# milliLearn-ice40-pcbng.net
KiCad netlist of a schematic drawn in EAGLE
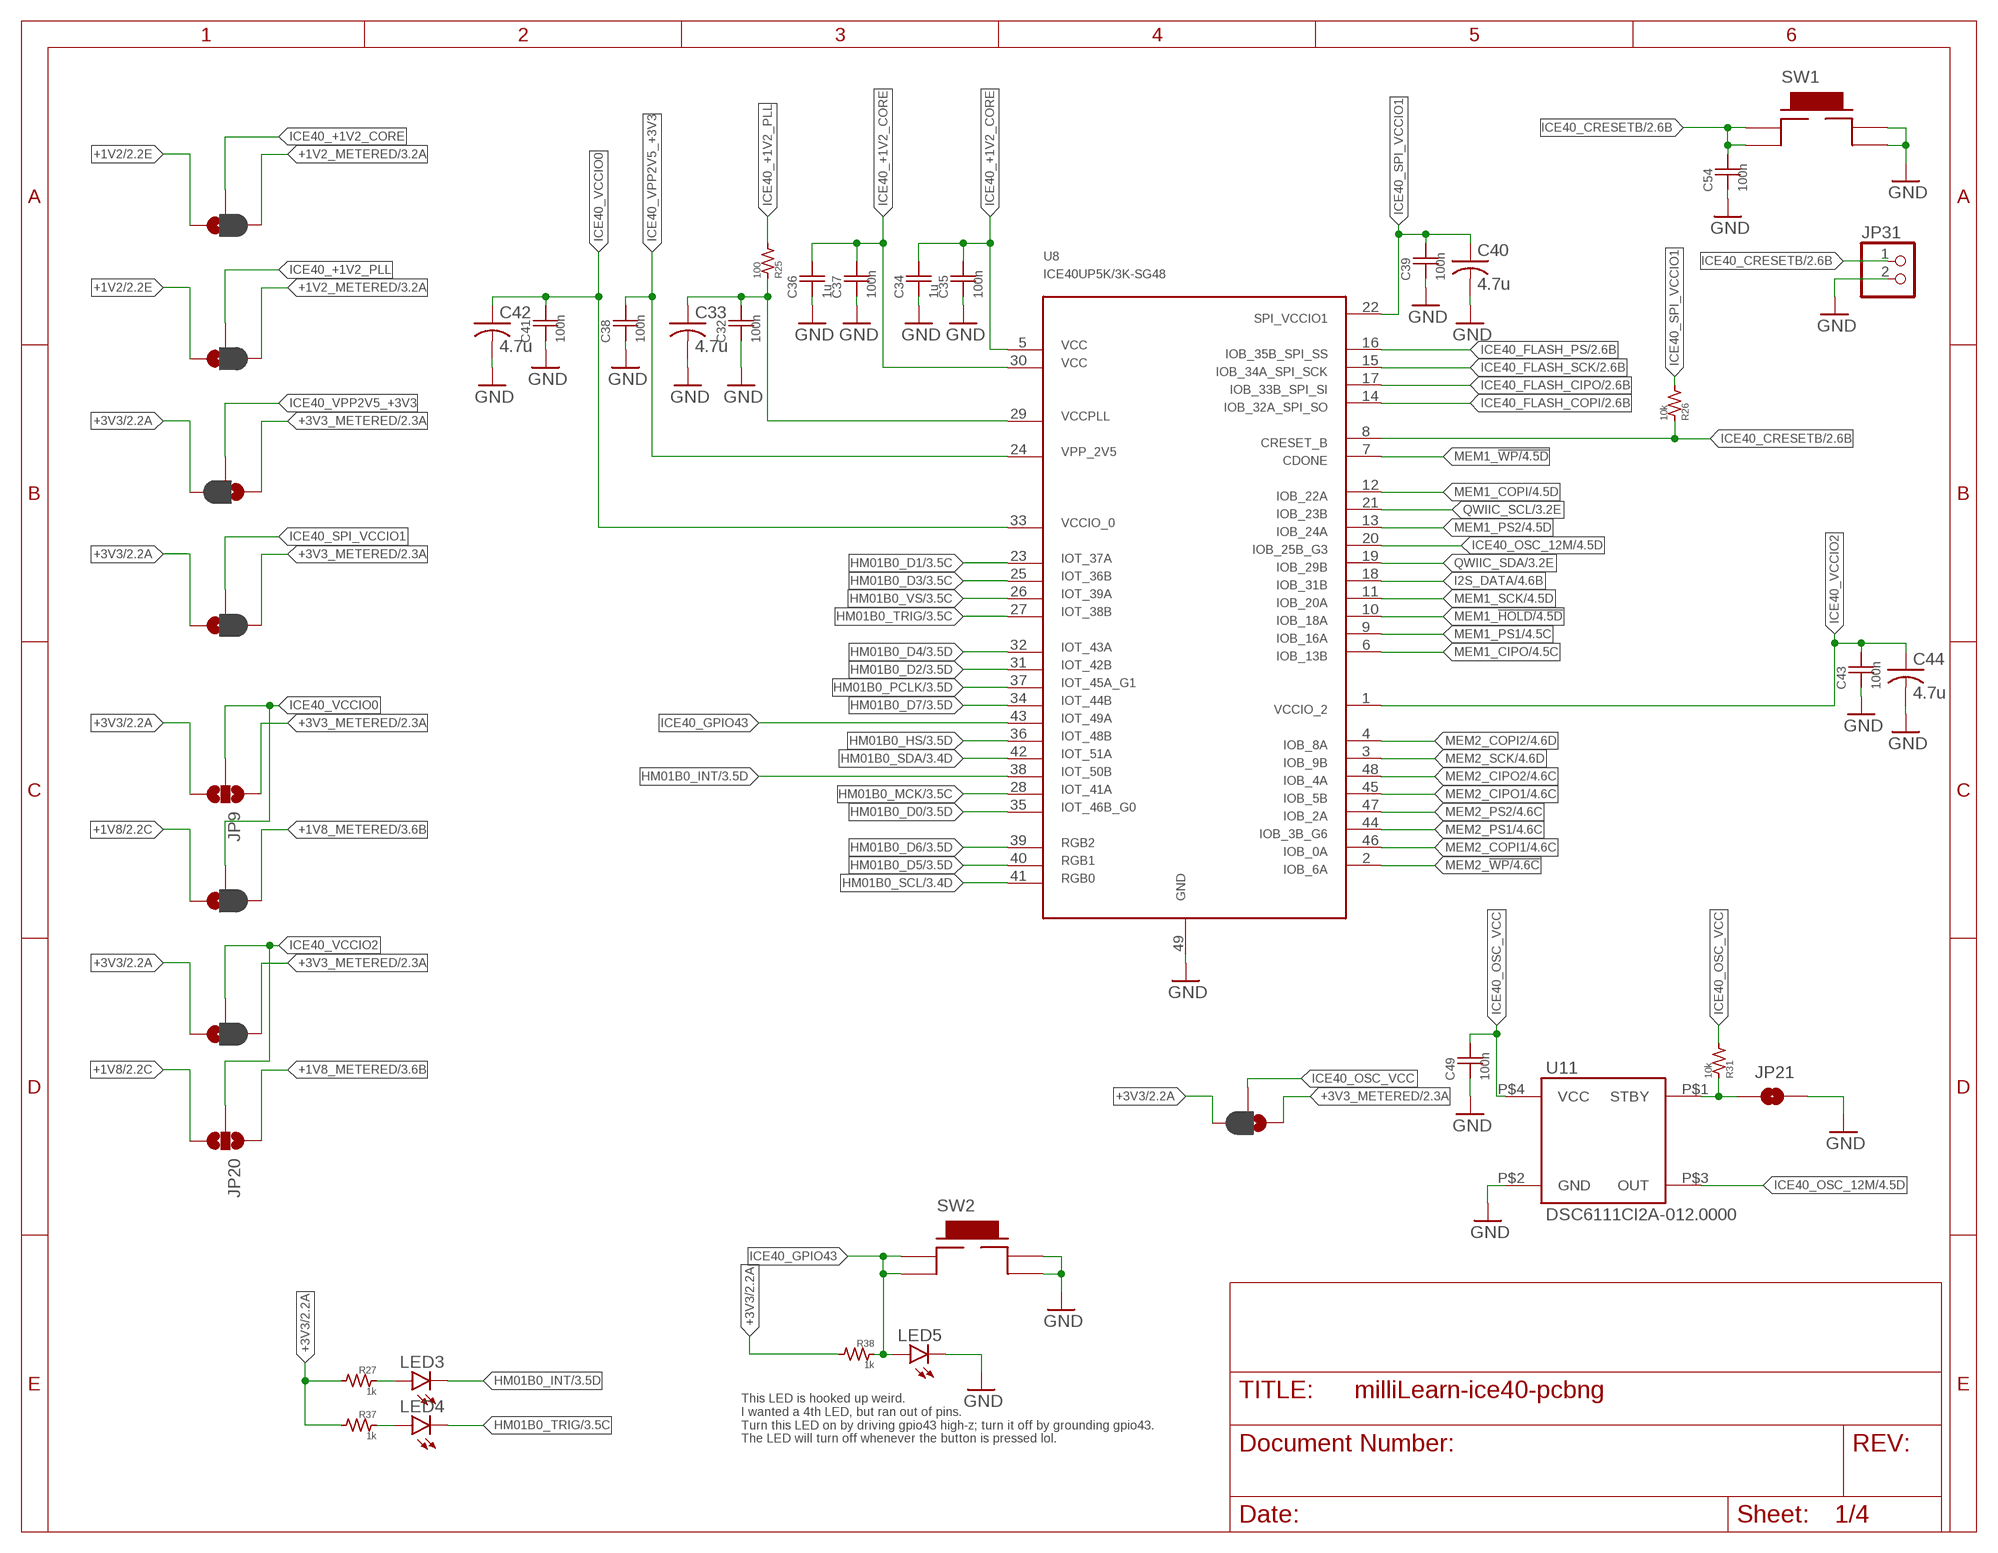
[diagram p0: schematic, sheet 1]
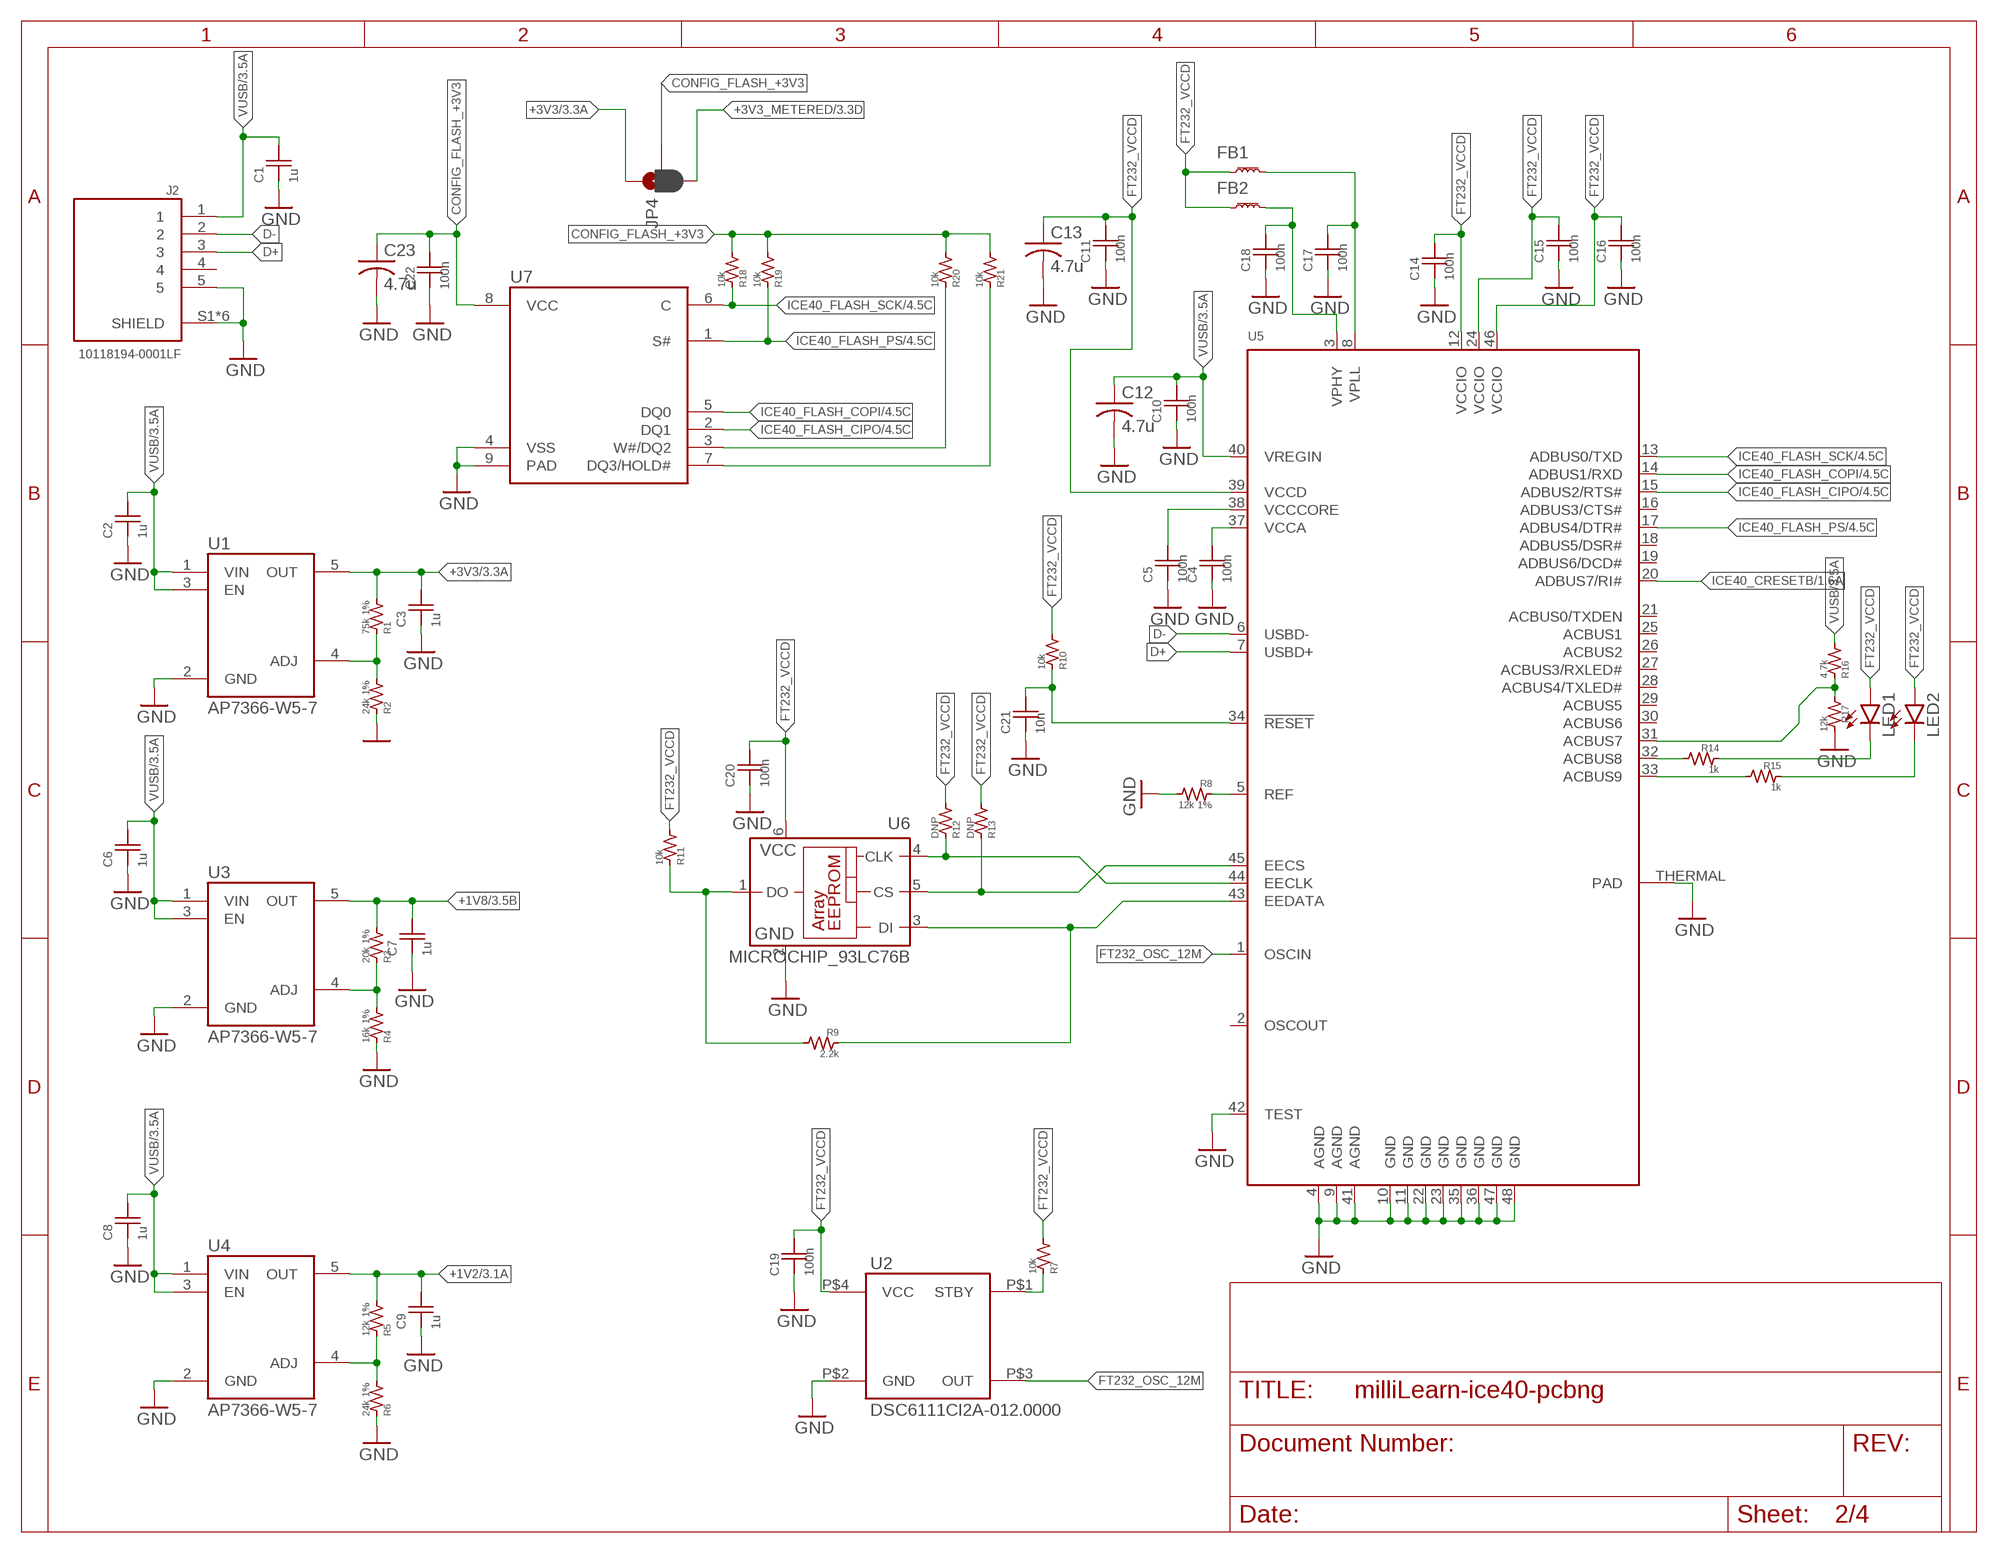
[diagram p1: schematic, sheet 2]
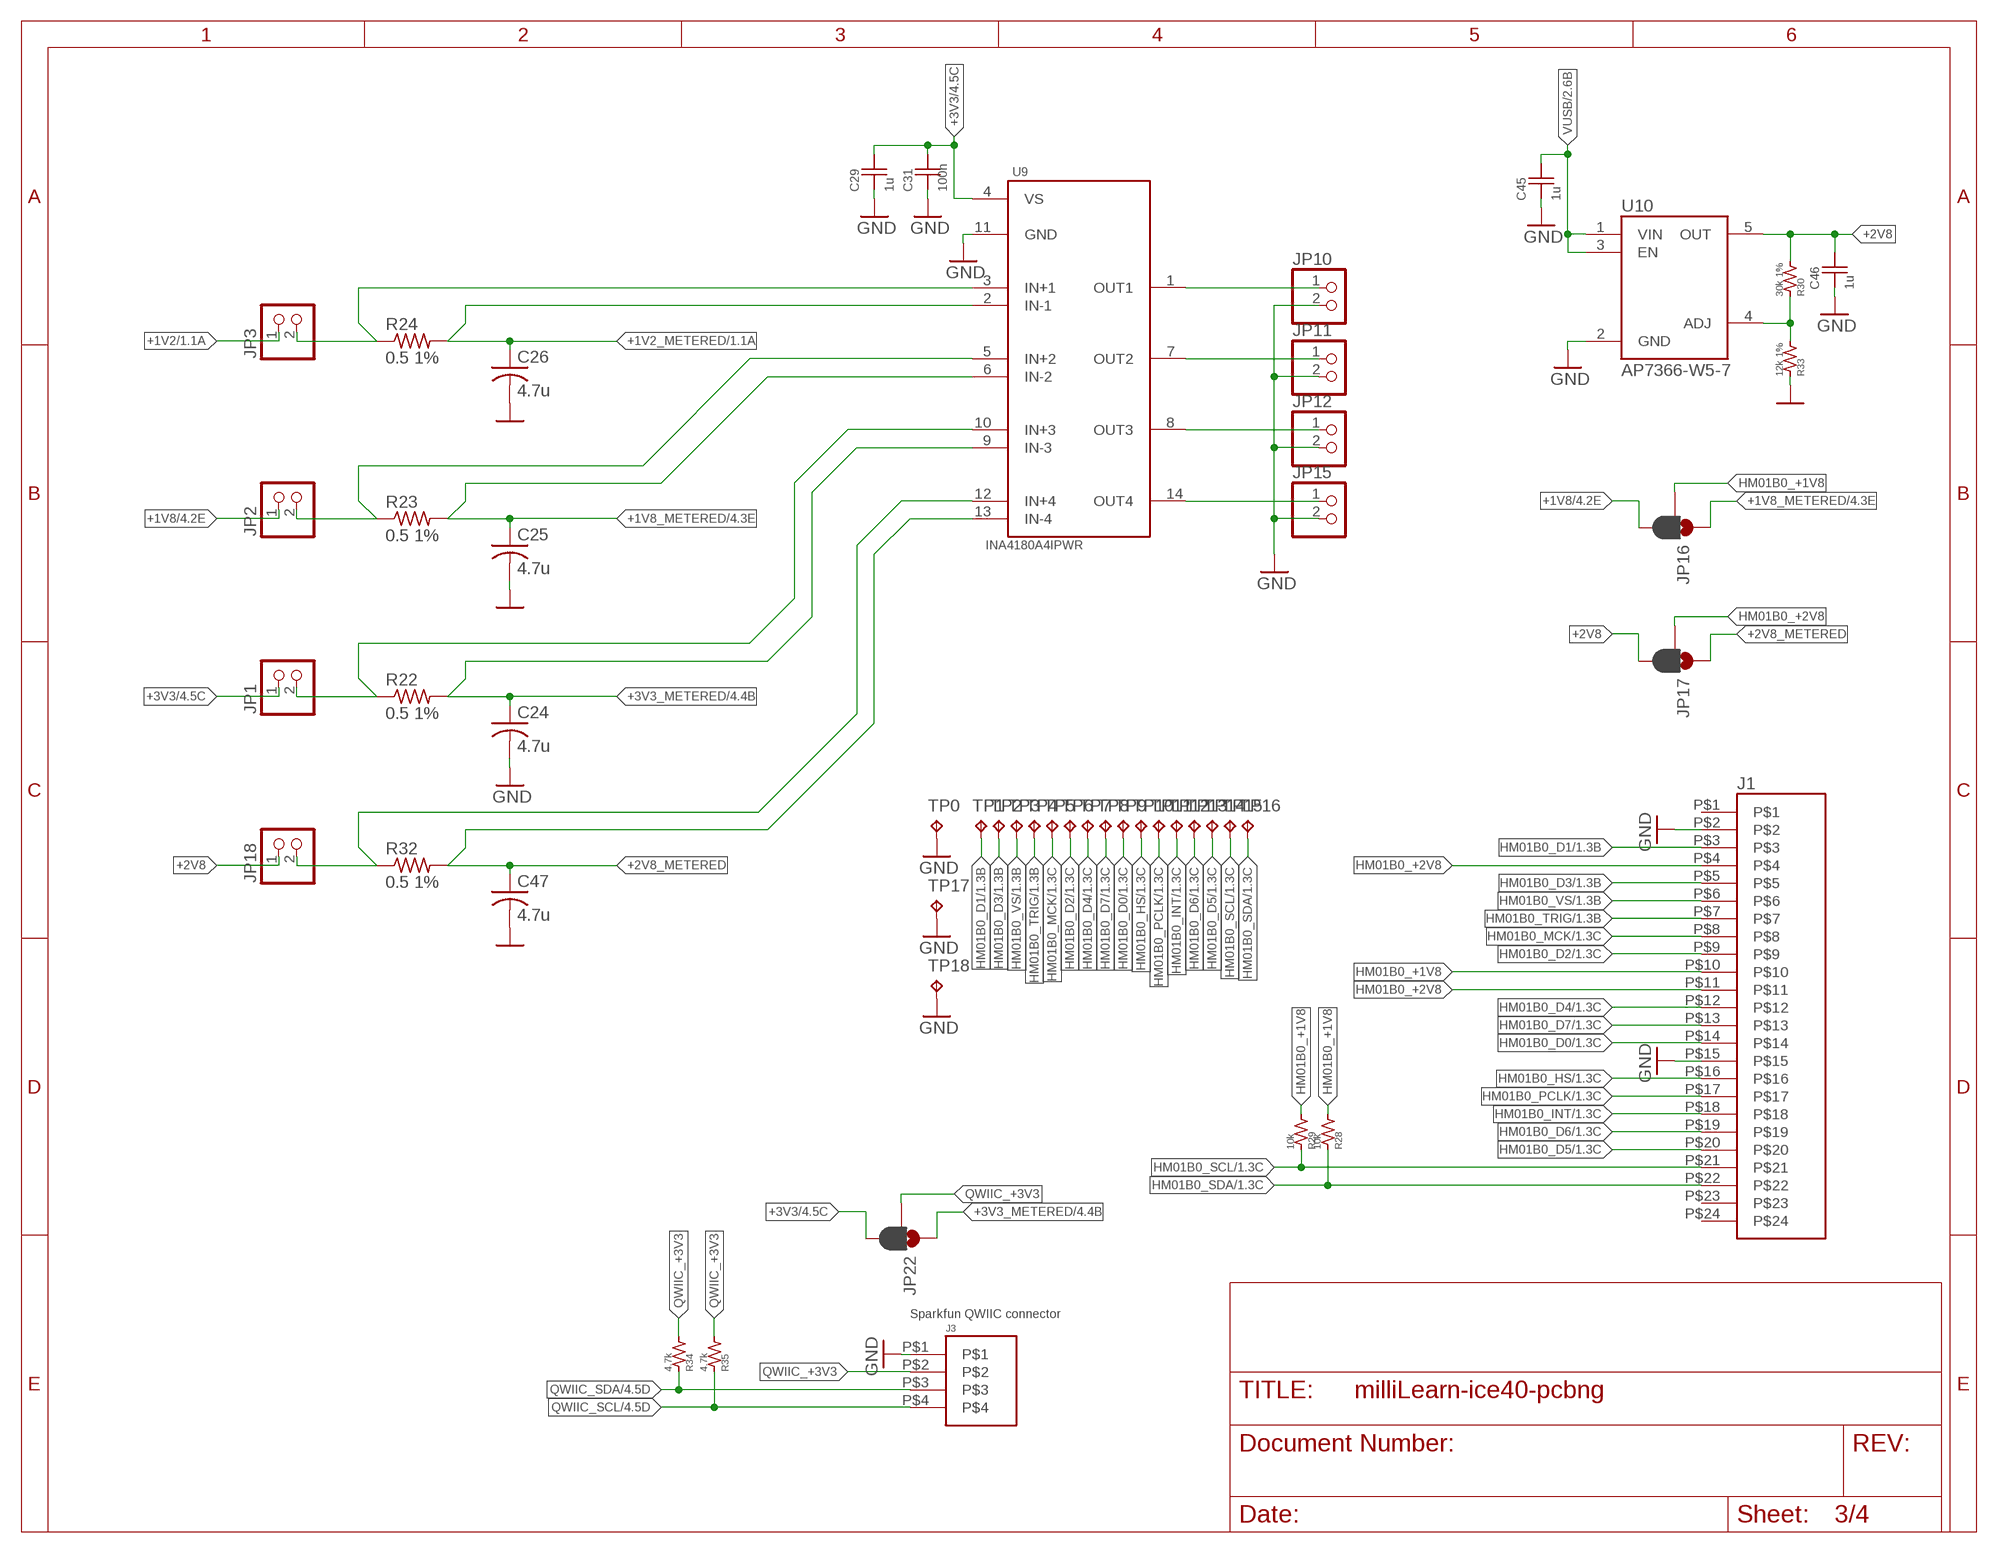
[diagram p2: schematic, sheet 3]
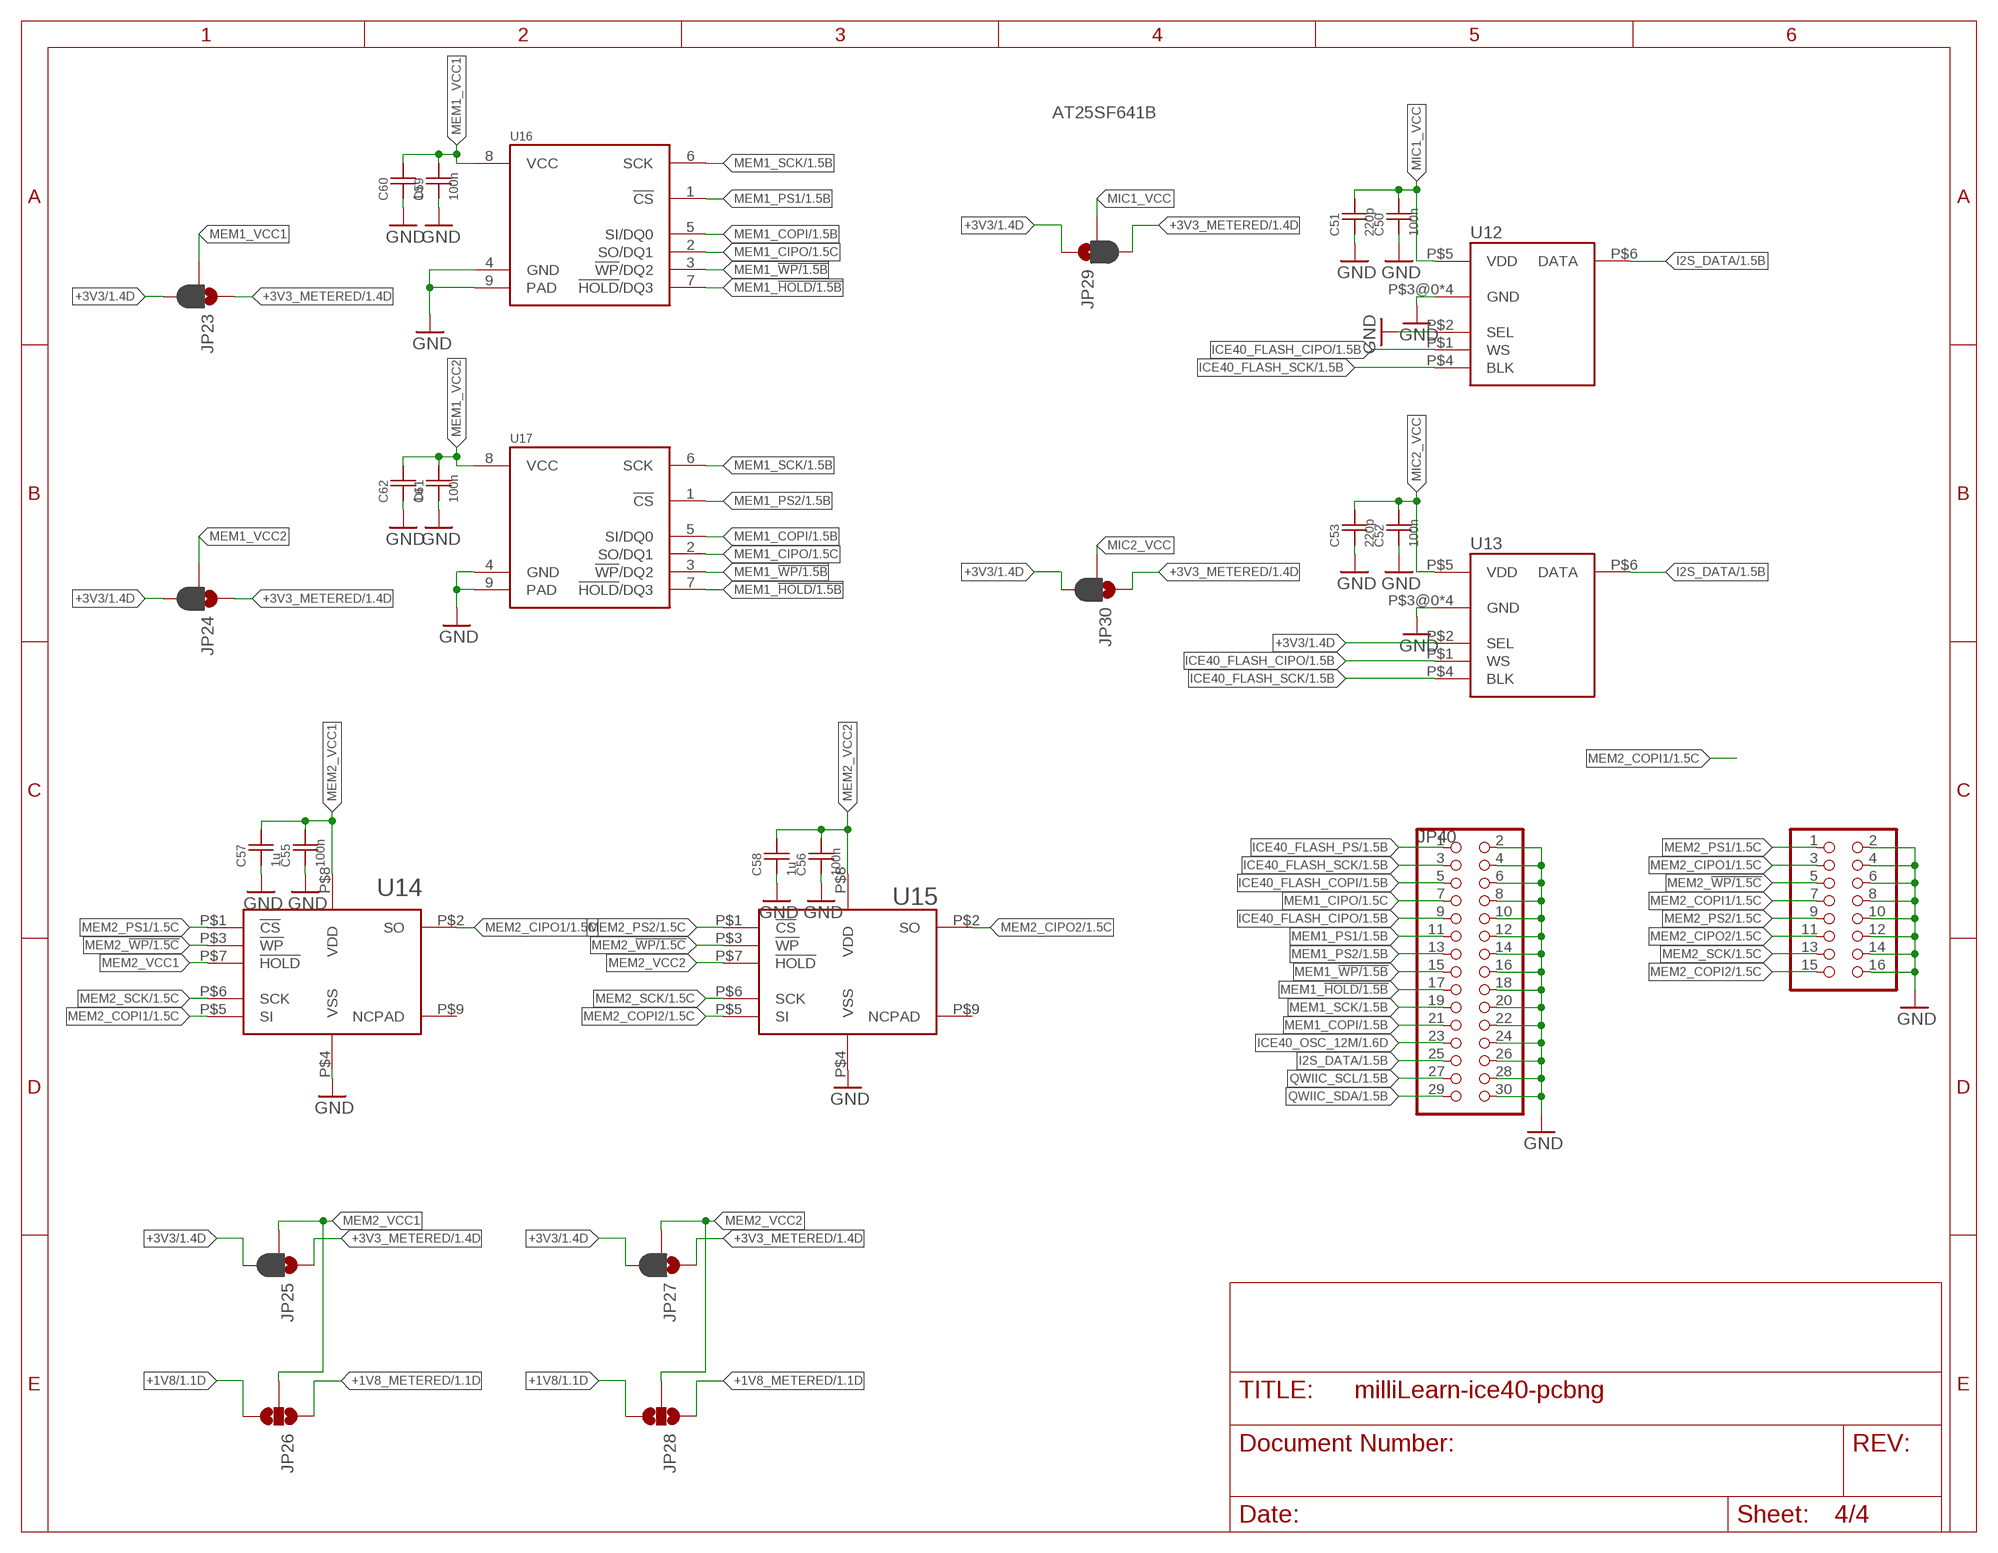
[diagram p3: schematic, sheet 4]

(export (version "E")
  (design (tool "Eeschema 10.0.6"))
  (components
    (comp (ref "C32")
      (value "100n")
      (footprint "eagle-import:C0402_COMPACT")
      (fields (field (name "MFR") "SAMSUNG"))
      (libsource (lib "eagle-import") (part "C0402_COMPACT"))
    )
    (comp (ref "C33")
      (value "4.7u")
      (footprint "eagle-import:C0603")
      (fields (field (name "MFR") "SAMSUNG"))
      (libsource (lib "eagle-import") (part "C-USC0603"))
    )
    (comp (ref "C34")
      (value "1u")
      (footprint "eagle-import:C0402_COMPACT")
      (fields (field (name "MFR") "SAMSUNG"))
      (libsource (lib "eagle-import") (part "C0402_COMPACT"))
    )
    (comp (ref "C35")
      (value "100n")
      (footprint "eagle-import:C0402_COMPACT")
      (fields (field (name "MFR") "SAMSUNG"))
      (libsource (lib "eagle-import") (part "C0402_COMPACT"))
    )
    (comp (ref "C36")
      (value "1u")
      (footprint "eagle-import:C0402_COMPACT")
      (fields (field (name "MFR") "SAMSUNG"))
      (libsource (lib "eagle-import") (part "C0402_COMPACT"))
    )
    (comp (ref "C37")
      (value "100n")
      (footprint "eagle-import:C0402_COMPACT")
      (fields (field (name "MFR") "SAMSUNG"))
      (libsource (lib "eagle-import") (part "C0402_COMPACT"))
    )
    (comp (ref "C38")
      (value "100n")
      (footprint "eagle-import:C0402_COMPACT")
      (fields (field (name "MFR") "SAMSUNG"))
      (libsource (lib "eagle-import") (part "C0402_COMPACT"))
    )
    (comp (ref "C39")
      (value "100n")
      (footprint "eagle-import:C0402_COMPACT")
      (fields (field (name "MFR") "SAMSUNG"))
      (libsource (lib "eagle-import") (part "C0402_COMPACT"))
    )
    (comp (ref "C40")
      (value "4.7u")
      (footprint "eagle-import:C0603")
      (fields (field (name "MFR") "SAMSUNG"))
      (libsource (lib "eagle-import") (part "C-USC0603"))
    )
    (comp (ref "C41")
      (value "100n")
      (footprint "eagle-import:C0402_COMPACT")
      (fields (field (name "MFR") "SAMSUNG"))
      (libsource (lib "eagle-import") (part "C0402_COMPACT"))
    )
    (comp (ref "C42")
      (value "4.7u")
      (footprint "eagle-import:C0603")
      (fields (field (name "MFR") "SAMSUNG"))
      (libsource (lib "eagle-import") (part "C-USC0603"))
    )
    (comp (ref "C43")
      (value "100n")
      (footprint "eagle-import:C0402_COMPACT")
      (fields (field (name "MFR") "SAMSUNG"))
      (libsource (lib "eagle-import") (part "C0402_COMPACT"))
    )
    (comp (ref "C44")
      (value "4.7u")
      (footprint "eagle-import:C0603")
      (fields (field (name "MFR") "SAMSUNG"))
      (libsource (lib "eagle-import") (part "C-USC0603"))
    )
    (comp (ref "C49")
      (value "100n")
      (footprint "eagle-import:C0402_COMPACT")
      (fields (field (name "MFR") "SAMSUNG"))
      (libsource (lib "eagle-import") (part "C0402_COMPACT"))
    )
    (comp (ref "C54")
      (value "100n")
      (footprint "eagle-import:C0402_COMPACT")
      (fields (field (name "MFR") "SAMSUNG"))
      (libsource (lib "eagle-import") (part "C0402_COMPACT"))
    )
    (comp (ref "JP5")
      (value "JUMPER-SMT_3_1-NC_PASTE_NO-SILK")
      (footprint "eagle-import:SMT-JUMPER_3_1-NC_PASTE_NO-SILK")
      (libsource (lib "eagle-import") (part "JUMPER-SMT_3_1-NC_PASTE_NO-SILK"))
    )
    (comp (ref "JP6")
      (value "JUMPER-SMT_3_1-NC_PASTE_NO-SILK")
      (footprint "eagle-import:SMT-JUMPER_3_1-NC_PASTE_NO-SILK")
      (libsource (lib "eagle-import") (part "JUMPER-SMT_3_1-NC_PASTE_NO-SILK"))
    )
    (comp (ref "JP7")
      (value "JUMPER-SMT_3_1-NC_PASTE_NO-SILK")
      (footprint "eagle-import:SMT-JUMPER_3_1-NC_PASTE_NO-SILK")
      (libsource (lib "eagle-import") (part "JUMPER-SMT_3_1-NC_PASTE_NO-SILK"))
    )
    (comp (ref "JP8")
      (value "JUMPER-SMT_3_1-NC_PASTE_NO-SILK")
      (footprint "eagle-import:SMT-JUMPER_3_1-NC_PASTE_NO-SILK")
      (libsource (lib "eagle-import") (part "JUMPER-SMT_3_1-NC_PASTE_NO-SILK"))
    )
    (comp (ref "JP9")
      (value "JUMPER-SMT_3_NO_NO-SILK")
      (footprint "eagle-import:SMT-JUMPER_3_NO_NO-SILK")
      (libsource (lib "eagle-import") (part "JUMPER-SMT_3_NO_NO-SILK"))
    )
    (comp (ref "JP13")
      (value "JUMPER-SMT_3_1-NC_PASTE_NO-SILK")
      (footprint "eagle-import:SMT-JUMPER_3_1-NC_PASTE_NO-SILK")
      (libsource (lib "eagle-import") (part "JUMPER-SMT_3_1-NC_PASTE_NO-SILK"))
    )
    (comp (ref "JP14")
      (value "JUMPER-SMT_3_1-NC_PASTE_NO-SILK")
      (footprint "eagle-import:SMT-JUMPER_3_1-NC_PASTE_NO-SILK")
      (libsource (lib "eagle-import") (part "JUMPER-SMT_3_1-NC_PASTE_NO-SILK"))
    )
    (comp (ref "JP19")
      (value "JUMPER-SMT_3_1-NC_PASTE_NO-SILK")
      (footprint "eagle-import:SMT-JUMPER_3_1-NC_PASTE_NO-SILK")
      (libsource (lib "eagle-import") (part "JUMPER-SMT_3_1-NC_PASTE_NO-SILK"))
    )
    (comp (ref "JP20")
      (value "JUMPER-SMT_3_NO_NO-SILK")
      (footprint "eagle-import:SMT-JUMPER_3_NO_NO-SILK")
      (libsource (lib "eagle-import") (part "JUMPER-SMT_3_NO_NO-SILK"))
    )
    (comp (ref "JP21")
      (value "JUMPER-SMT_2_NO_NO-SILK")
      (footprint "eagle-import:SMT-JUMPER_2_NO_NO-SILK")
      (libsource (lib "eagle-import") (part "JUMPER-SMT_2_NO_NO-SILK"))
    )
    (comp (ref "JP31")
      (value "PINHD-1X2")
      (footprint "eagle-import:1X02")
      (libsource (lib "eagle-import") (part "PINHD-1X2"))
    )
    (comp (ref "LED3")
      (value "LEDCHIPLED_0603")
      (footprint "eagle-import:CHIPLED_0603")
      (fields (field (name "MFR") "LITE-ON"))
      (libsource (lib "eagle-import") (part "LEDCHIPLED_0603"))
    )
    (comp (ref "LED4")
      (value "LEDCHIPLED_0603")
      (footprint "eagle-import:CHIPLED_0603")
      (fields (field (name "MFR") "LITE-ON"))
      (libsource (lib "eagle-import") (part "LEDCHIPLED_0603"))
    )
    (comp (ref "LED5")
      (value "LEDCHIPLED_0603")
      (footprint "eagle-import:CHIPLED_0603")
      (fields (field (name "MFR") "LITE-ON"))
      (libsource (lib "eagle-import") (part "LEDCHIPLED_0603"))
    )
    (comp (ref "R25")
      (value "100")
      (footprint "eagle-import:R0402_COMPACT")
      (fields (field (name "MFR") "YAGEO"))
      (libsource (lib "eagle-import") (part "R0402_COMPACT"))
    )
    (comp (ref "R26")
      (value "10k")
      (footprint "eagle-import:R0402_COMPACT")
      (fields (field (name "MFR") "PANASONIC"))
      (libsource (lib "eagle-import") (part "R0402_COMPACT"))
    )
    (comp (ref "R27")
      (value "1k")
      (footprint "eagle-import:R0402_COMPACT")
      (fields (field (name "MFR") "PANASONIC"))
      (libsource (lib "eagle-import") (part "R0402_COMPACT"))
    )
    (comp (ref "R31")
      (value "10k")
      (footprint "eagle-import:R0402_COMPACT")
      (fields (field (name "MFR") "PANASONIC"))
      (libsource (lib "eagle-import") (part "R0402_COMPACT"))
    )
    (comp (ref "R37")
      (value "1k")
      (footprint "eagle-import:R0402_COMPACT")
      (fields (field (name "MFR") "PANASONIC"))
      (libsource (lib "eagle-import") (part "R0402_COMPACT"))
    )
    (comp (ref "R38")
      (value "1k")
      (footprint "eagle-import:R0402_COMPACT")
      (fields (field (name "MFR") "PANASONIC"))
      (libsource (lib "eagle-import") (part "R0402_COMPACT"))
    )
    (comp (ref "SW1")
      (value "TE_FSMJSMA")
      (footprint "eagle-import:TE_FSMJSMA")
      (fields (field (name "MFR") "TE"))
      (libsource (lib "eagle-import") (part "TE_FSMJSMA"))
    )
    (comp (ref "SW2")
      (value "TE_FSMJSMA")
      (footprint "eagle-import:TE_FSMJSMA")
      (fields (field (name "MFR") "TE"))
      (libsource (lib "eagle-import") (part "TE_FSMJSMA"))
    )
    (comp (ref "U8")
      (value "ICE40UP5K/3K-SG48")
      (footprint "eagle-import:ICE40UP5K_3K-SG48")
      (fields (field (name "MFR") "LATTICE"))
      (libsource (lib "eagle-import") (part "ICE40UP5K/3K-SG48"))
    )
    (comp (ref "U11")
      (value "DSC6111CI2A-012.0000")
      (footprint "eagle-import:DSC6111CI2A-012.0000")
      (fields (field (name "MFR") "MICROCHIP"))
      (libsource (lib "eagle-import") (part "DSC6111CI2A-012.0000"))
    )
    (comp (ref "C24")
      (value "4.7u")
      (footprint "eagle-import:C0603")
      (fields (field (name "MFR") "SAMSUNG"))
      (libsource (lib "eagle-import") (part "C-USC0603"))
    )
    (comp (ref "C25")
      (value "4.7u")
      (footprint "eagle-import:C0603")
      (fields (field (name "MFR") "SAMSUNG"))
      (libsource (lib "eagle-import") (part "C-USC0603"))
    )
    (comp (ref "C26")
      (value "4.7u")
      (footprint "eagle-import:C0603")
      (fields (field (name "MFR") "SAMSUNG"))
      (libsource (lib "eagle-import") (part "C-USC0603"))
    )
    (comp (ref "C29")
      (value "1u")
      (footprint "eagle-import:C0402_COMPACT")
      (fields (field (name "MFR") "SAMSUNG"))
      (libsource (lib "eagle-import") (part "C0402_COMPACT"))
    )
    (comp (ref "C31")
      (value "100n")
      (footprint "eagle-import:C0402_COMPACT")
      (fields (field (name "MFR") "SAMSUNG"))
      (libsource (lib "eagle-import") (part "C0402_COMPACT"))
    )
    (comp (ref "C45")
      (value "1u")
      (footprint "eagle-import:C0402_COMPACT")
      (fields (field (name "MFR") "SAMSUNG"))
      (libsource (lib "eagle-import") (part "C0402_COMPACT"))
    )
    (comp (ref "C46")
      (value "1u")
      (footprint "eagle-import:C0402_COMPACT")
      (fields (field (name "MFR") "SAMSUNG"))
      (libsource (lib "eagle-import") (part "C0402_COMPACT"))
    )
    (comp (ref "C47")
      (value "4.7u")
      (footprint "eagle-import:C0603")
      (fields (field (name "MFR") "SAMSUNG"))
      (libsource (lib "eagle-import") (part "C-USC0603"))
    )
    (comp (ref "J1")
      (value "SFV24R-2STE1HLF")
      (footprint "eagle-import:SFV24R-2STE1HLF")
      (fields (field (name "MFR") "AMPHENOL"))
      (libsource (lib "eagle-import") (part "SFV24R-2STE1HLF"))
    )
    (comp (ref "J3")
      (value "SM04B-SRSS-TB(LF)(SN)")
      (footprint "eagle-import:SM04B-SRSS-TB(LF)(SN)")
      (fields (field (name "MFR") "JST"))
      (libsource (lib "eagle-import") (part "SM04B-SRSS-TB(LF)(SN)"))
    )
    (comp (ref "JP1")
      (value "PINHD-1X2")
      (footprint "eagle-import:1X02")
      (fields (field (name "MFR") "WURTH ELECTRONIK"))
      (libsource (lib "eagle-import") (part "PINHD-1X2"))
    )
    (comp (ref "JP2")
      (value "PINHD-1X2")
      (footprint "eagle-import:1X02")
      (fields (field (name "MFR") "WURTH ELECTRONIK"))
      (libsource (lib "eagle-import") (part "PINHD-1X2"))
    )
    (comp (ref "JP3")
      (value "PINHD-1X2")
      (footprint "eagle-import:1X02")
      (fields (field (name "MFR") "WURTH ELECTRONIK"))
      (libsource (lib "eagle-import") (part "PINHD-1X2"))
    )
    (comp (ref "JP10")
      (value "PINHD-1X2")
      (footprint "eagle-import:1X02")
      (fields (field (name "MFR") "WURTH ELECTRONIK"))
      (libsource (lib "eagle-import") (part "PINHD-1X2"))
    )
    (comp (ref "JP11")
      (value "PINHD-1X2")
      (footprint "eagle-import:1X02")
      (fields (field (name "MFR") "WURTH ELECTRONIK"))
      (libsource (lib "eagle-import") (part "PINHD-1X2"))
    )
    (comp (ref "JP12")
      (value "PINHD-1X2")
      (footprint "eagle-import:1X02")
      (fields (field (name "MFR") "WURTH ELECTRONIK"))
      (libsource (lib "eagle-import") (part "PINHD-1X2"))
    )
    (comp (ref "JP15")
      (value "PINHD-1X2")
      (footprint "eagle-import:1X02")
      (fields (field (name "MFR") "WURTH ELECTRONIK"))
      (libsource (lib "eagle-import") (part "PINHD-1X2"))
    )
    (comp (ref "JP16")
      (value "JUMPER-SMT_3_1-NC_PASTE_NO-SILK")
      (footprint "eagle-import:SMT-JUMPER_3_1-NC_PASTE_NO-SILK")
      (libsource (lib "eagle-import") (part "JUMPER-SMT_3_1-NC_PASTE_NO-SILK"))
    )
    (comp (ref "JP17")
      (value "JUMPER-SMT_3_1-NC_PASTE_NO-SILK")
      (footprint "eagle-import:SMT-JUMPER_3_1-NC_PASTE_NO-SILK")
      (libsource (lib "eagle-import") (part "JUMPER-SMT_3_1-NC_PASTE_NO-SILK"))
    )
    (comp (ref "JP18")
      (value "PINHD-1X2")
      (footprint "eagle-import:1X02")
      (fields (field (name "MFR") "WURTH ELECTRONIK"))
      (libsource (lib "eagle-import") (part "PINHD-1X2"))
    )
    (comp (ref "JP22")
      (value "JUMPER-SMT_3_1-NC_PASTE_NO-SILK")
      (footprint "eagle-import:SMT-JUMPER_3_1-NC_PASTE_NO-SILK")
      (libsource (lib "eagle-import") (part "JUMPER-SMT_3_1-NC_PASTE_NO-SILK"))
    )
    (comp (ref "R22")
      (value "0.5 1%")
      (footprint "eagle-import:R0603")
      (fields (field (name "MFR") "YAGEO"))
      (libsource (lib "eagle-import") (part "R-US_R0603"))
    )
    (comp (ref "R23")
      (value "0.5 1%")
      (footprint "eagle-import:R0603")
      (fields (field (name "MFR") "YAGEO"))
      (libsource (lib "eagle-import") (part "R-US_R0603"))
    )
    (comp (ref "R24")
      (value "0.5 1%")
      (footprint "eagle-import:R0603")
      (fields (field (name "MFR") "YAGEO"))
      (libsource (lib "eagle-import") (part "R-US_R0603"))
    )
    (comp (ref "R28")
      (value "10k")
      (footprint "eagle-import:R0402_COMPACT")
      (fields (field (name "MFR") "PANASONIC"))
      (libsource (lib "eagle-import") (part "R0402_COMPACT"))
    )
    (comp (ref "R29")
      (value "10k")
      (footprint "eagle-import:R0402_COMPACT")
      (fields (field (name "MFR") "PANASONIC"))
      (libsource (lib "eagle-import") (part "R0402_COMPACT"))
    )
    (comp (ref "R30")
      (value "30k 1%")
      (footprint "eagle-import:R0402_COMPACT")
      (fields (field (name "MFR") "PANASONIC"))
      (libsource (lib "eagle-import") (part "R0402_COMPACT"))
    )
    (comp (ref "R32")
      (value "0.5 1%")
      (footprint "eagle-import:R0603")
      (fields (field (name "MFR") "YAGEO"))
      (libsource (lib "eagle-import") (part "R-US_R0603"))
    )
    (comp (ref "R33")
      (value "12k 1%")
      (footprint "eagle-import:R0402_COMPACT")
      (fields (field (name "MFR") "PANASONIC"))
      (libsource (lib "eagle-import") (part "R0402_COMPACT"))
    )
    (comp (ref "R34")
      (value "4.7k")
      (footprint "eagle-import:R0402_COMPACT")
      (fields (field (name "MFR") "PANASONIC"))
      (libsource (lib "eagle-import") (part "R0402_COMPACT"))
    )
    (comp (ref "R35")
      (value "4.7k")
      (footprint "eagle-import:R0402_COMPACT")
      (fields (field (name "MFR") "PANASONIC"))
      (libsource (lib "eagle-import") (part "R0402_COMPACT"))
    )
    (comp (ref "TP0")
      (value "TPTP10SQ")
      (footprint "eagle-import:TP10SQ")
      (libsource (lib "eagle-import") (part "TPTP10SQ"))
    )
    (comp (ref "TP1")
      (value "TPTP10SQ")
      (footprint "eagle-import:TP10SQ")
      (libsource (lib "eagle-import") (part "TPTP10SQ"))
    )
    (comp (ref "TP2")
      (value "TPTP10SQ")
      (footprint "eagle-import:TP10SQ")
      (libsource (lib "eagle-import") (part "TPTP10SQ"))
    )
    (comp (ref "TP3")
      (value "TPTP10SQ")
      (footprint "eagle-import:TP10SQ")
      (libsource (lib "eagle-import") (part "TPTP10SQ"))
    )
    (comp (ref "TP4")
      (value "TPTP10SQ")
      (footprint "eagle-import:TP10SQ")
      (libsource (lib "eagle-import") (part "TPTP10SQ"))
    )
    (comp (ref "TP5")
      (value "TPTP10SQ")
      (footprint "eagle-import:TP10SQ")
      (libsource (lib "eagle-import") (part "TPTP10SQ"))
    )
    (comp (ref "TP6")
      (value "TPTP10SQ")
      (footprint "eagle-import:TP10SQ")
      (libsource (lib "eagle-import") (part "TPTP10SQ"))
    )
    (comp (ref "TP7")
      (value "TPTP10SQ")
      (footprint "eagle-import:TP10SQ")
      (libsource (lib "eagle-import") (part "TPTP10SQ"))
    )
    (comp (ref "TP8")
      (value "TPTP10SQ")
      (footprint "eagle-import:TP10SQ")
      (libsource (lib "eagle-import") (part "TPTP10SQ"))
    )
    (comp (ref "TP9")
      (value "TPTP10SQ")
      (footprint "eagle-import:TP10SQ")
      (libsource (lib "eagle-import") (part "TPTP10SQ"))
    )
    (comp (ref "TP10")
      (value "TPTP10SQ")
      (footprint "eagle-import:TP10SQ")
      (libsource (lib "eagle-import") (part "TPTP10SQ"))
    )
    (comp (ref "TP11")
      (value "TPTP10SQ")
      (footprint "eagle-import:TP10SQ")
      (libsource (lib "eagle-import") (part "TPTP10SQ"))
    )
    (comp (ref "TP12")
      (value "TPTP10SQ")
      (footprint "eagle-import:TP10SQ")
      (libsource (lib "eagle-import") (part "TPTP10SQ"))
    )
    (comp (ref "TP13")
      (value "TPTP10SQ")
      (footprint "eagle-import:TP10SQ")
      (libsource (lib "eagle-import") (part "TPTP10SQ"))
    )
    (comp (ref "TP14")
      (value "TPTP10SQ")
      (footprint "eagle-import:TP10SQ")
      (libsource (lib "eagle-import") (part "TPTP10SQ"))
    )
    (comp (ref "TP15")
      (value "TPTP10SQ")
      (footprint "eagle-import:TP10SQ")
      (libsource (lib "eagle-import") (part "TPTP10SQ"))
    )
    (comp (ref "TP16")
      (value "TPTP10SQ")
      (footprint "eagle-import:TP10SQ")
      (libsource (lib "eagle-import") (part "TPTP10SQ"))
    )
    (comp (ref "TP17")
      (value "TPTP10SQ")
      (footprint "eagle-import:TP10SQ")
      (libsource (lib "eagle-import") (part "TPTP10SQ"))
    )
    (comp (ref "TP18")
      (value "TPTP10SQ")
      (footprint "eagle-import:TP10SQ")
      (libsource (lib "eagle-import") (part "TPTP10SQ"))
    )
    (comp (ref "U9")
      (value "INA4180A4IPWR")
      (footprint "eagle-import:INA4180A4IPWR")
      (fields (field (name "MFR") "TI"))
      (libsource (lib "eagle-import") (part "INA4180A4IPWR"))
    )
    (comp (ref "U10")
      (value "AP7366-W5-7")
      (footprint "eagle-import:AP7366-W5-7")
      (fields (field (name "MFR") "Diodes Inc"))
      (libsource (lib "eagle-import") (part "AP7366-W5-7"))
    )
    (comp (ref "C50")
      (value "100n")
      (footprint "eagle-import:C0402_COMPACT")
      (fields (field (name "MFR") "SAMSUNG"))
      (libsource (lib "eagle-import") (part "C0402_COMPACT"))
    )
    (comp (ref "C51")
      (value "220p")
      (footprint "eagle-import:C0402_COMPACT")
      (fields (field (name "MFR") "SAMSUNG"))
      (libsource (lib "eagle-import") (part "C0402_COMPACT"))
    )
    (comp (ref "C52")
      (value "100n")
      (footprint "eagle-import:C0402_COMPACT")
      (fields (field (name "MFR") "SAMSUNG"))
      (libsource (lib "eagle-import") (part "C0402_COMPACT"))
    )
    (comp (ref "C53")
      (value "220p")
      (footprint "eagle-import:C0402_COMPACT")
      (fields (field (name "MFR") "SAMSUNG"))
      (libsource (lib "eagle-import") (part "C0402_COMPACT"))
    )
    (comp (ref "C55")
      (value "100n")
      (footprint "eagle-import:C0402_COMPACT")
      (fields (field (name "MFR") "SAMSUNG"))
      (libsource (lib "eagle-import") (part "C0402_COMPACT"))
    )
    (comp (ref "C56")
      (value "100n")
      (footprint "eagle-import:C0402_COMPACT")
      (fields (field (name "MFR") "SAMSUNG"))
      (libsource (lib "eagle-import") (part "C0402_COMPACT"))
    )
    (comp (ref "C57")
      (value "1u")
      (footprint "eagle-import:C0402_COMPACT")
      (fields (field (name "MFR") "SAMSUNG"))
      (libsource (lib "eagle-import") (part "C0402_COMPACT"))
    )
    (comp (ref "C58")
      (value "1u")
      (footprint "eagle-import:C0402_COMPACT")
      (fields (field (name "MFR") "SAMSUNG"))
      (libsource (lib "eagle-import") (part "C0402_COMPACT"))
    )
    (comp (ref "C59")
      (value "100n")
      (footprint "eagle-import:C0402_COMPACT")
      (fields (field (name "MFR") "SAMSUNG"))
      (libsource (lib "eagle-import") (part "C0402_COMPACT"))
    )
    (comp (ref "C60")
      (value "1u")
      (footprint "eagle-import:C0402_COMPACT")
      (fields (field (name "MFR") "SAMSUNG"))
      (libsource (lib "eagle-import") (part "C0402_COMPACT"))
    )
    (comp (ref "C61")
      (value "100n")
      (footprint "eagle-import:C0402_COMPACT")
      (fields (field (name "MFR") "SAMSUNG"))
      (libsource (lib "eagle-import") (part "C0402_COMPACT"))
    )
    (comp (ref "C62")
      (value "1u")
      (footprint "eagle-import:C0402_COMPACT")
      (fields (field (name "MFR") "SAMSUNG"))
      (libsource (lib "eagle-import") (part "C0402_COMPACT"))
    )
    (comp (ref "JP23")
      (value "JUMPER-SMT_3_1-NC_PASTE_NO-SILK")
      (footprint "eagle-import:SMT-JUMPER_3_1-NC_PASTE_NO-SILK")
      (libsource (lib "eagle-import") (part "JUMPER-SMT_3_1-NC_PASTE_NO-SILK"))
    )
    (comp (ref "JP24")
      (value "JUMPER-SMT_3_1-NC_PASTE_NO-SILK")
      (footprint "eagle-import:SMT-JUMPER_3_1-NC_PASTE_NO-SILK")
      (libsource (lib "eagle-import") (part "JUMPER-SMT_3_1-NC_PASTE_NO-SILK"))
    )
    (comp (ref "JP25")
      (value "JUMPER-SMT_3_1-NC_PASTE_NO-SILK")
      (footprint "eagle-import:SMT-JUMPER_3_1-NC_PASTE_NO-SILK")
      (libsource (lib "eagle-import") (part "JUMPER-SMT_3_1-NC_PASTE_NO-SILK"))
    )
    (comp (ref "JP26")
      (value "JUMPER-SMT_3_NO_NO-SILK")
      (footprint "eagle-import:SMT-JUMPER_3_NO_NO-SILK")
      (libsource (lib "eagle-import") (part "JUMPER-SMT_3_NO_NO-SILK"))
    )
    (comp (ref "JP27")
      (value "JUMPER-SMT_3_1-NC_PASTE_NO-SILK")
      (footprint "eagle-import:SMT-JUMPER_3_1-NC_PASTE_NO-SILK")
      (libsource (lib "eagle-import") (part "JUMPER-SMT_3_1-NC_PASTE_NO-SILK"))
    )
    (comp (ref "JP28")
      (value "JUMPER-SMT_3_NO_NO-SILK")
      (footprint "eagle-import:SMT-JUMPER_3_NO_NO-SILK")
      (libsource (lib "eagle-import") (part "JUMPER-SMT_3_NO_NO-SILK"))
    )
    (comp (ref "JP29")
      (value "JUMPER-SMT_3_1-NC_PASTE_NO-SILK")
      (footprint "eagle-import:SMT-JUMPER_3_1-NC_PASTE_NO-SILK")
      (libsource (lib "eagle-import") (part "JUMPER-SMT_3_1-NC_PASTE_NO-SILK"))
    )
    (comp (ref "JP30")
      (value "JUMPER-SMT_3_1-NC_PASTE_NO-SILK")
      (footprint "eagle-import:SMT-JUMPER_3_1-NC_PASTE_NO-SILK")
      (libsource (lib "eagle-import") (part "JUMPER-SMT_3_1-NC_PASTE_NO-SILK"))
    )
    (comp (ref "JP40")
      (value "PINHD-2X15")
      (footprint "eagle-import:2X15")
      (libsource (lib "eagle-import") (part "PINHD-2X15"))
    )
    (comp (ref "JP41")
      (value "PINHD-2X8")
      (footprint "eagle-import:2X08")
      (libsource (lib "eagle-import") (part "PINHD-2X8"))
    )
    (comp (ref "U12")
      (value "SPH0645LM4H-B")
      (footprint "eagle-import:SPH0645LM4H-B")
      (fields (field (name "MFR") "KNOWLES"))
      (libsource (lib "eagle-import") (part "SPH0645LM4H-B"))
    )
    (comp (ref "U13")
      (value "SPH0645LM4H-B")
      (footprint "eagle-import:SPH0645LM4H-B")
      (fields (field (name "MFR") "KNOWLES"))
      (libsource (lib "eagle-import") (part "SPH0645LM4H-B"))
    )
    (comp (ref "U14")
      (value "CY15B104Q-LHXI")
      (footprint "eagle-import:CY15B104Q-LHXI")
      (fields (field (name "MANUFACTURER") "Cypress") (field (name "MFR") "CYPRESS"))
      (libsource (lib "eagle-import") (part "CY15B104Q-LHXI"))
    )
    (comp (ref "U15")
      (value "CY15B104Q-LHXI")
      (footprint "eagle-import:CY15B104Q-LHXI")
      (fields (field (name "MANUFACTURER") "Cypress") (field (name "MFR") "CYPRESS"))
      (libsource (lib "eagle-import") (part "CY15B104Q-LHXI"))
    )
    (comp (ref "U16")
      (value "AT25QF641B-SHB-T")
      (footprint "eagle-import:AT25QF641B-SHB-T")
      (fields (field (name "MFR") "ADESTO"))
      (libsource (lib "eagle-import") (part "AT25QF641B-SHB-T"))
    )
    (comp (ref "U17")
      (value "AT25QF641B-SHB-T")
      (footprint "eagle-import:AT25QF641B-SHB-T")
      (fields (field (name "MFR") "ADESTO"))
      (libsource (lib "eagle-import") (part "AT25QF641B-SHB-T"))
    )
    (comp (ref "C1")
      (value "1u")
      (footprint "eagle-import:C0402_COMPACT")
      (fields (field (name "MFR") "SAMSUNG"))
      (libsource (lib "eagle-import") (part "C0402_COMPACT"))
    )
    (comp (ref "C2")
      (value "1u")
      (footprint "eagle-import:C0402_COMPACT")
      (fields (field (name "MFR") "SAMSUNG"))
      (libsource (lib "eagle-import") (part "C0402_COMPACT"))
    )
    (comp (ref "C3")
      (value "1u")
      (footprint "eagle-import:C0402_COMPACT")
      (fields (field (name "MFR") "SAMSUNG"))
      (libsource (lib "eagle-import") (part "C0402_COMPACT"))
    )
    (comp (ref "C4")
      (value "100n")
      (footprint "eagle-import:C0402_COMPACT")
      (fields (field (name "MFR") "SAMSUNG"))
      (libsource (lib "eagle-import") (part "C0402_COMPACT"))
    )
    (comp (ref "C5")
      (value "100n")
      (footprint "eagle-import:C0402_COMPACT")
      (fields (field (name "MFR") "SAMSUNG"))
      (libsource (lib "eagle-import") (part "C0402_COMPACT"))
    )
    (comp (ref "C6")
      (value "1u")
      (footprint "eagle-import:C0402_COMPACT")
      (fields (field (name "MFR") "SAMSUNG"))
      (libsource (lib "eagle-import") (part "C0402_COMPACT"))
    )
    (comp (ref "C7")
      (value "1u")
      (footprint "eagle-import:C0402_COMPACT")
      (fields (field (name "MFR") "SAMSUNG"))
      (libsource (lib "eagle-import") (part "C0402_COMPACT"))
    )
    (comp (ref "C8")
      (value "1u")
      (footprint "eagle-import:C0402_COMPACT")
      (fields (field (name "MFR") "SAMSUNG"))
      (libsource (lib "eagle-import") (part "C0402_COMPACT"))
    )
    (comp (ref "C9")
      (value "1u")
      (footprint "eagle-import:C0402_COMPACT")
      (fields (field (name "MFR") "SAMSUNG"))
      (libsource (lib "eagle-import") (part "C0402_COMPACT"))
    )
    (comp (ref "C10")
      (value "100n")
      (footprint "eagle-import:C0402_COMPACT")
      (fields (field (name "MFR") "SAMSUNG"))
      (libsource (lib "eagle-import") (part "C0402_COMPACT"))
    )
    (comp (ref "C11")
      (value "100n")
      (footprint "eagle-import:C0402_COMPACT")
      (fields (field (name "MFR") "SAMSUNG"))
      (libsource (lib "eagle-import") (part "C0402_COMPACT"))
    )
    (comp (ref "C12")
      (value "4.7u")
      (footprint "eagle-import:C0603")
      (fields (field (name "MFR") "SAMSUNG"))
      (libsource (lib "eagle-import") (part "C-USC0603"))
    )
    (comp (ref "C13")
      (value "4.7u")
      (footprint "eagle-import:C0603")
      (fields (field (name "MFR") "SAMSUNG"))
      (libsource (lib "eagle-import") (part "C-USC0603"))
    )
    (comp (ref "C14")
      (value "100n")
      (footprint "eagle-import:C0402_COMPACT")
      (fields (field (name "MFR") "SAMSUNG"))
      (libsource (lib "eagle-import") (part "C0402_COMPACT"))
    )
    (comp (ref "C15")
      (value "100n")
      (footprint "eagle-import:C0402_COMPACT")
      (fields (field (name "MFR") "SAMSUNG"))
      (libsource (lib "eagle-import") (part "C0402_COMPACT"))
    )
    (comp (ref "C16")
      (value "100n")
      (footprint "eagle-import:C0402_COMPACT")
      (fields (field (name "MFR") "SAMSUNG"))
      (libsource (lib "eagle-import") (part "C0402_COMPACT"))
    )
    (comp (ref "C17")
      (value "100n")
      (footprint "eagle-import:C0402_COMPACT")
      (fields (field (name "MFR") "SAMSUNG"))
      (libsource (lib "eagle-import") (part "C0402_COMPACT"))
    )
    (comp (ref "C18")
      (value "100n")
      (footprint "eagle-import:C0402_COMPACT")
      (fields (field (name "MFR") "SAMSUNG"))
      (libsource (lib "eagle-import") (part "C0402_COMPACT"))
    )
    (comp (ref "C19")
      (value "100n")
      (footprint "eagle-import:C0402_COMPACT")
      (fields (field (name "MFR") "SAMSUNG"))
      (libsource (lib "eagle-import") (part "C0402_COMPACT"))
    )
    (comp (ref "C20")
      (value "100n")
      (footprint "eagle-import:C0402_COMPACT")
      (fields (field (name "MFR") "SAMSUNG"))
      (libsource (lib "eagle-import") (part "C0402_COMPACT"))
    )
    (comp (ref "C21")
      (value "10n")
      (footprint "eagle-import:C0402_COMPACT")
      (fields (field (name "MFR") "SAMSUNG"))
      (libsource (lib "eagle-import") (part "C0402_COMPACT"))
    )
    (comp (ref "C22")
      (value "100n")
      (footprint "eagle-import:C0402_COMPACT")
      (fields (field (name "MFR") "SAMSUNG"))
      (libsource (lib "eagle-import") (part "C0402_COMPACT"))
    )
    (comp (ref "C23")
      (value "4.7u")
      (footprint "eagle-import:C0603")
      (fields (field (name "MFR") "SAMSUNG"))
      (libsource (lib "eagle-import") (part "C-USC0603"))
    )
    (comp (ref "FB1")
      (value "BLM18KG601SN1D")
      (footprint "eagle-import:BLM18KG601SN1D")
      (fields (field (name "MFR") "MURATA"))
      (libsource (lib "eagle-import") (part "BLM18KG601SN1D"))
    )
    (comp (ref "FB2")
      (value "BLM18KG601SN1D")
      (footprint "eagle-import:BLM18KG601SN1D")
      (fields (field (name "MFR") "MURATA"))
      (libsource (lib "eagle-import") (part "BLM18KG601SN1D"))
    )
    (comp (ref "J2")
      (value "10118194-0001LF")
      (footprint "eagle-import:AMPHENOL_10118194-0001LF")
      (fields (field (name "MF") "Amphenol ICC"))
      (libsource (lib "eagle-import") (part "10118194-0001LF"))
    )
    (comp (ref "JP4")
      (value "JUMPER-SMT_3_1-NC_PASTE_NO-SILK")
      (footprint "eagle-import:SMT-JUMPER_3_1-NC_PASTE_NO-SILK")
      (libsource (lib "eagle-import") (part "JUMPER-SMT_3_1-NC_PASTE_NO-SILK"))
    )
    (comp (ref "LED1")
      (value "LEDCHIPLED_0603")
      (footprint "eagle-import:CHIPLED_0603")
      (fields (field (name "MFR") "LITE-ON"))
      (libsource (lib "eagle-import") (part "LEDCHIPLED_0603"))
    )
    (comp (ref "LED2")
      (value "LEDCHIPLED_0603")
      (footprint "eagle-import:CHIPLED_0603")
      (fields (field (name "MFR") "LITE-ON"))
      (libsource (lib "eagle-import") (part "LEDCHIPLED_0603"))
    )
    (comp (ref "R1")
      (value "75k 1%")
      (footprint "eagle-import:R0402_COMPACT")
      (fields (field (name "MFR") "PANASONIC"))
      (libsource (lib "eagle-import") (part "R0402_COMPACT"))
    )
    (comp (ref "R2")
      (value "24k 1%")
      (footprint "eagle-import:R0402_COMPACT")
      (fields (field (name "MFR") "PANASONIC"))
      (libsource (lib "eagle-import") (part "R0402_COMPACT"))
    )
    (comp (ref "R3")
      (value "20k 1%")
      (footprint "eagle-import:R0402_COMPACT")
      (fields (field (name "MFR") "PANASONIC"))
      (libsource (lib "eagle-import") (part "R0402_COMPACT"))
    )
    (comp (ref "R4")
      (value "16k 1%")
      (footprint "eagle-import:R0402_COMPACT")
      (fields (field (name "MFR") "PANASONIC"))
      (libsource (lib "eagle-import") (part "R0402_COMPACT"))
    )
    (comp (ref "R5")
      (value "12k 1%")
      (footprint "eagle-import:R0402_COMPACT")
      (fields (field (name "MFR") "PANASONIC"))
      (libsource (lib "eagle-import") (part "R0402_COMPACT"))
    )
    (comp (ref "R6")
      (value "24k 1%")
      (footprint "eagle-import:R0402_COMPACT")
      (fields (field (name "MFR") "PANASONIC"))
      (libsource (lib "eagle-import") (part "R0402_COMPACT"))
    )
    (comp (ref "R7")
      (value "10k")
      (footprint "eagle-import:R0402_COMPACT")
      (fields (field (name "MFR") "PANASONIC"))
      (libsource (lib "eagle-import") (part "R0402_COMPACT"))
    )
    (comp (ref "R8")
      (value "12k 1%")
      (footprint "eagle-import:R0402_COMPACT")
      (fields (field (name "MFR") "PANASONIC"))
      (libsource (lib "eagle-import") (part "R0402_COMPACT"))
    )
    (comp (ref "R9")
      (value "2.2k")
      (footprint "eagle-import:R0402_COMPACT")
      (fields (field (name "MFR") "PANASONIC"))
      (libsource (lib "eagle-import") (part "R0402_COMPACT"))
    )
    (comp (ref "R10")
      (value "10k")
      (footprint "eagle-import:R0402_COMPACT")
      (fields (field (name "MFR") "PANASONIC"))
      (libsource (lib "eagle-import") (part "R0402_COMPACT"))
    )
    (comp (ref "R11")
      (value "10k")
      (footprint "eagle-import:R0402_COMPACT")
      (fields (field (name "MFR") "PANASONIC"))
      (libsource (lib "eagle-import") (part "R0402_COMPACT"))
    )
    (comp (ref "R12")
      (value "DNP")
      (footprint "eagle-import:R0402_COMPACT")
      (fields (field (name "MFR") "PANASONIC"))
      (libsource (lib "eagle-import") (part "R0402_COMPACT"))
    )
    (comp (ref "R13")
      (value "DNP")
      (footprint "eagle-import:R0402_COMPACT")
      (fields (field (name "MFR") "PANASONIC"))
      (libsource (lib "eagle-import") (part "R0402_COMPACT"))
    )
    (comp (ref "R14")
      (value "1k")
      (footprint "eagle-import:R0402_COMPACT")
      (fields (field (name "MFR") "PANASONIC"))
      (libsource (lib "eagle-import") (part "R0402_COMPACT"))
    )
    (comp (ref "R15")
      (value "1k")
      (footprint "eagle-import:R0402_COMPACT")
      (fields (field (name "MFR") "PANASONIC"))
      (libsource (lib "eagle-import") (part "R0402_COMPACT"))
    )
    (comp (ref "R16")
      (value "4.7k")
      (footprint "eagle-import:R0402_COMPACT")
      (fields (field (name "MFR") "PANASONIC"))
      (libsource (lib "eagle-import") (part "R0402_COMPACT"))
    )
    (comp (ref "R17")
      (value "12k")
      (footprint "eagle-import:R0402_COMPACT")
      (fields (field (name "MFR") "PANASONIC"))
      (libsource (lib "eagle-import") (part "R0402_COMPACT"))
    )
    (comp (ref "R18")
      (value "10k")
      (footprint "eagle-import:R0402_COMPACT")
      (fields (field (name "MFR") "PANASONIC"))
      (libsource (lib "eagle-import") (part "R0402_COMPACT"))
    )
    (comp (ref "R19")
      (value "10k")
      (footprint "eagle-import:R0402_COMPACT")
      (fields (field (name "MFR") "PANASONIC"))
      (libsource (lib "eagle-import") (part "R0402_COMPACT"))
    )
    (comp (ref "R20")
      (value "10k")
      (footprint "eagle-import:R0402_COMPACT")
      (fields (field (name "MFR") "PANASONIC"))
      (libsource (lib "eagle-import") (part "R0402_COMPACT"))
    )
    (comp (ref "R21")
      (value "10k")
      (footprint "eagle-import:R0402_COMPACT")
      (fields (field (name "MFR") "PANASONIC"))
      (libsource (lib "eagle-import") (part "R0402_COMPACT"))
    )
    (comp (ref "U1")
      (value "AP7366-W5-7")
      (footprint "eagle-import:AP7366-W5-7")
      (fields (field (name "MFR") "Diodes Inc"))
      (libsource (lib "eagle-import") (part "AP7366-W5-7"))
    )
    (comp (ref "U2")
      (value "DSC6111CI2A-012.0000")
      (footprint "eagle-import:DSC6111CI2A-012.0000")
      (fields (field (name "MFR") "MICROCHIP"))
      (libsource (lib "eagle-import") (part "DSC6111CI2A-012.0000"))
    )
    (comp (ref "U3")
      (value "AP7366-W5-7")
      (footprint "eagle-import:AP7366-W5-7")
      (fields (field (name "MFR") "Diodes Inc"))
      (libsource (lib "eagle-import") (part "AP7366-W5-7"))
    )
    (comp (ref "U4")
      (value "AP7366-W5-7")
      (footprint "eagle-import:AP7366-W5-7")
      (fields (field (name "MFR") "Diodes Inc"))
      (libsource (lib "eagle-import") (part "AP7366-W5-7"))
    )
    (comp (ref "U5")
      (value "MICROBUILDER_FT232HQ")
      (footprint "eagle-import:MICROBUILDER_QFN48_8MM")
      (fields (field (name "MFR") "FTDI"))
      (libsource (lib "eagle-import") (part "MICROBUILDER_FT232HQ"))
    )
    (comp (ref "U6")
      (value "MICROCHIP_93LC76B")
      (footprint "eagle-import:MICROCHIP_SOT23-6")
      (fields (field (name "MF") "MICROCHIP") (field (name "MPN") "93LC76BT-I/OT"))
      (libsource (lib "eagle-import") (part "MICROCHIP_9376?BLC"))
    )
    (comp (ref "U7")
      (value "MT25QL128ABA1EW7")
      (footprint "eagle-import:MT25QL128ABA1EW7")
      (fields (field (name "MFR") "MICRON"))
      (libsource (lib "eagle-import") (part "MT25QL128ABA1EW7"))
    )
  )
  (nets
    (net (code "1") (name "+1V2") (class "Default")
      (node (ref "C9") (pin "2") (pinfunction "P$2_2") (pintype "bidirectional"))
      (node (ref "JP3") (pin "1") (pinfunction "1_1") (pintype "passive"))
      (node (ref "JP5") (pin "1") (pinfunction "1_1") (pintype "passive"))
      (node (ref "JP6") (pin "1") (pinfunction "1_1") (pintype "passive"))
      (node (ref "R5") (pin "1") (pinfunction "P$1_1") (pintype "bidirectional"))
      (node (ref "U4") (pin "5") (pinfunction "OUT_5") (pintype "bidirectional"))
    )
    (net (code "2") (name "+1V2_METERED") (class "Default")
      (node (ref "C26") (pin "1") (pinfunction "1_1") (pintype "passive"))
      (node (ref "JP5") (pin "3") (pinfunction "3_3") (pintype "passive"))
      (node (ref "JP6") (pin "3") (pinfunction "3_3") (pintype "passive"))
      (node (ref "R24") (pin "2") (pinfunction "2_2") (pintype "passive"))
      (node (ref "U9") (pin "2") (pinfunction "IN-1_2") (pintype "bidirectional"))
    )
    (net (code "3") (name "+1V8") (class "Default")
      (node (ref "C7") (pin "2") (pinfunction "P$2_2") (pintype "bidirectional"))
      (node (ref "JP13") (pin "1") (pinfunction "1_1") (pintype "passive"))
      (node (ref "JP16") (pin "3") (pinfunction "3_3") (pintype "passive"))
      (node (ref "JP2") (pin "1") (pinfunction "1_1") (pintype "passive"))
      (node (ref "JP20") (pin "3") (pinfunction "3_3") (pintype "passive"))
      (node (ref "JP26") (pin "3") (pinfunction "3_3") (pintype "passive"))
      (node (ref "JP28") (pin "3") (pinfunction "3_3") (pintype "passive"))
      (node (ref "R3") (pin "1") (pinfunction "P$1_1") (pintype "bidirectional"))
      (node (ref "U3") (pin "5") (pinfunction "OUT_5") (pintype "bidirectional"))
    )
    (net (code "4") (name "+1V8_METERED") (class "Default")
      (node (ref "C25") (pin "1") (pinfunction "1_1") (pintype "passive"))
      (node (ref "JP13") (pin "3") (pinfunction "3_3") (pintype "passive"))
      (node (ref "JP16") (pin "1") (pinfunction "1_1") (pintype "passive"))
      (node (ref "JP20") (pin "1") (pinfunction "1_1") (pintype "passive"))
      (node (ref "JP26") (pin "1") (pinfunction "1_1") (pintype "passive"))
      (node (ref "JP28") (pin "1") (pinfunction "1_1") (pintype "passive"))
      (node (ref "R23") (pin "2") (pinfunction "2_2") (pintype "passive"))
      (node (ref "U9") (pin "6") (pinfunction "IN-2_6") (pintype "bidirectional"))
    )
    (net (code "5") (name "+2V8") (class "Default")
      (node (ref "C46") (pin "2") (pinfunction "P$2_2") (pintype "bidirectional"))
      (node (ref "JP17") (pin "3") (pinfunction "3_3") (pintype "passive"))
      (node (ref "JP18") (pin "1") (pinfunction "1_1") (pintype "passive"))
      (node (ref "R30") (pin "1") (pinfunction "P$1_1") (pintype "bidirectional"))
      (node (ref "U10") (pin "5") (pinfunction "OUT_5") (pintype "bidirectional"))
    )
    (net (code "6") (name "+2V8_METERED") (class "Default")
      (node (ref "C47") (pin "1") (pinfunction "1_1") (pintype "passive"))
      (node (ref "JP17") (pin "1") (pinfunction "1_1") (pintype "passive"))
      (node (ref "R32") (pin "2") (pinfunction "2_2") (pintype "passive"))
      (node (ref "U9") (pin "13") (pinfunction "IN-4_13") (pintype "bidirectional"))
    )
    (net (code "7") (name "+3V3") (class "Default")
      (node (ref "C29") (pin "2") (pinfunction "P$2_2") (pintype "bidirectional"))
      (node (ref "C3") (pin "2") (pinfunction "P$2_2") (pintype "bidirectional"))
      (node (ref "C31") (pin "2") (pinfunction "P$2_2") (pintype "bidirectional"))
      (node (ref "JP1") (pin "1") (pinfunction "1_1") (pintype "passive"))
      (node (ref "JP14") (pin "1") (pinfunction "1_1") (pintype "passive"))
      (node (ref "JP19") (pin "3") (pinfunction "3_3") (pintype "passive"))
      (node (ref "JP22") (pin "3") (pinfunction "3_3") (pintype "passive"))
      (node (ref "JP23") (pin "3") (pinfunction "3_3") (pintype "passive"))
      (node (ref "JP24") (pin "3") (pinfunction "3_3") (pintype "passive"))
      (node (ref "JP25") (pin "3") (pinfunction "3_3") (pintype "passive"))
      (node (ref "JP27") (pin "3") (pinfunction "3_3") (pintype "passive"))
      (node (ref "JP29") (pin "1") (pinfunction "1_1") (pintype "passive"))
      (node (ref "JP30") (pin "3") (pinfunction "3_3") (pintype "passive"))
      (node (ref "JP4") (pin "1") (pinfunction "1_1") (pintype "passive"))
      (node (ref "JP7") (pin "3") (pinfunction "3_3") (pintype "passive"))
      (node (ref "JP8") (pin "1") (pinfunction "1_1") (pintype "passive"))
      (node (ref "JP9") (pin "3") (pinfunction "3_3") (pintype "passive"))
      (node (ref "R1") (pin "1") (pinfunction "P$1_1") (pintype "bidirectional"))
      (node (ref "R27") (pin "1") (pinfunction "P$1_1") (pintype "bidirectional"))
      (node (ref "R37") (pin "1") (pinfunction "P$1_1") (pintype "bidirectional"))
      (node (ref "R38") (pin "1") (pinfunction "P$1_1") (pintype "bidirectional"))
      (node (ref "U1") (pin "5") (pinfunction "OUT_5") (pintype "bidirectional"))
      (node (ref "U13") (pin "P$2") (pinfunction "SEL_P$2") (pintype "bidirectional"))
      (node (ref "U9") (pin "4") (pinfunction "VS_4") (pintype "bidirectional"))
    )
    (net (code "8") (name "+3V3_METERED") (class "Default")
      (node (ref "C24") (pin "1") (pinfunction "1_1") (pintype "passive"))
      (node (ref "JP14") (pin "3") (pinfunction "3_3") (pintype "passive"))
      (node (ref "JP19") (pin "1") (pinfunction "1_1") (pintype "passive"))
      (node (ref "JP22") (pin "1") (pinfunction "1_1") (pintype "passive"))
      (node (ref "JP23") (pin "1") (pinfunction "1_1") (pintype "passive"))
      (node (ref "JP24") (pin "1") (pinfunction "1_1") (pintype "passive"))
      (node (ref "JP25") (pin "1") (pinfunction "1_1") (pintype "passive"))
      (node (ref "JP27") (pin "1") (pinfunction "1_1") (pintype "passive"))
      (node (ref "JP29") (pin "3") (pinfunction "3_3") (pintype "passive"))
      (node (ref "JP30") (pin "1") (pinfunction "1_1") (pintype "passive"))
      (node (ref "JP4") (pin "3") (pinfunction "3_3") (pintype "passive"))
      (node (ref "JP7") (pin "1") (pinfunction "1_1") (pintype "passive"))
      (node (ref "JP8") (pin "3") (pinfunction "3_3") (pintype "passive"))
      (node (ref "JP9") (pin "1") (pinfunction "1_1") (pintype "passive"))
      (node (ref "R22") (pin "2") (pinfunction "2_2") (pintype "passive"))
      (node (ref "U9") (pin "9") (pinfunction "IN-3_9") (pintype "bidirectional"))
    )
    (net (code "9") (name "CONFIG_FLASH_+3V3") (class "Default")
      (node (ref "C22") (pin "2") (pinfunction "P$2_2") (pintype "bidirectional"))
      (node (ref "C23") (pin "1") (pinfunction "1_1") (pintype "passive"))
      (node (ref "JP4") (pin "2") (pinfunction "2_2") (pintype "passive"))
      (node (ref "R18") (pin "1") (pinfunction "P$1_1") (pintype "bidirectional"))
      (node (ref "R19") (pin "1") (pinfunction "P$1_1") (pintype "bidirectional"))
      (node (ref "R20") (pin "1") (pinfunction "P$1_1") (pintype "bidirectional"))
      (node (ref "R21") (pin "1") (pinfunction "P$1_1") (pintype "bidirectional"))
      (node (ref "U7") (pin "8") (pinfunction "VCC_8") (pintype "bidirectional"))
    )
    (net (code "10") (name "D+") (class "Default")
      (node (ref "J2") (pin "3") (pinfunction "3_3") (pintype "passive"))
      (node (ref "U5") (pin "7") (pinfunction "USBD+_7") (pintype "bidirectional"))
    )
    (net (code "11") (name "D-") (class "Default")
      (node (ref "J2") (pin "2") (pinfunction "2_2") (pintype "passive"))
      (node (ref "U5") (pin "6") (pinfunction "USBD-_6") (pintype "bidirectional"))
    )
    (net (code "12") (name "FT232_OSC_12M") (class "Default")
      (node (ref "U2") (pin "P$3") (pinfunction "OUT_P$3") (pintype "bidirectional"))
      (node (ref "U5") (pin "1") (pinfunction "OSCIN_1") (pintype "input"))
    )
    (net (code "13") (name "FT232_VCCD") (class "Default")
      (node (ref "C11") (pin "2") (pinfunction "P$2_2") (pintype "bidirectional"))
      (node (ref "C13") (pin "1") (pinfunction "1_1") (pintype "passive"))
      (node (ref "C14") (pin "2") (pinfunction "P$2_2") (pintype "bidirectional"))
      (node (ref "C15") (pin "2") (pinfunction "P$2_2") (pintype "bidirectional"))
      (node (ref "C16") (pin "2") (pinfunction "P$2_2") (pintype "bidirectional"))
      (node (ref "C19") (pin "2") (pinfunction "P$2_2") (pintype "bidirectional"))
      (node (ref "C20") (pin "2") (pinfunction "P$2_2") (pintype "bidirectional"))
      (node (ref "FB1") (pin "1") (pinfunction "P$1_1") (pintype "bidirectional"))
      (node (ref "FB2") (pin "1") (pinfunction "P$1_1") (pintype "bidirectional"))
      (node (ref "LED1") (pin "A") (pinfunction "A_A") (pintype "passive"))
      (node (ref "LED2") (pin "A") (pinfunction "A_A") (pintype "passive"))
      (node (ref "R10") (pin "1") (pinfunction "P$1_1") (pintype "bidirectional"))
      (node (ref "R11") (pin "1") (pinfunction "P$1_1") (pintype "bidirectional"))
      (node (ref "R12") (pin "1") (pinfunction "P$1_1") (pintype "bidirectional"))
      (node (ref "R13") (pin "1") (pinfunction "P$1_1") (pintype "bidirectional"))
      (node (ref "R7") (pin "1") (pinfunction "P$1_1") (pintype "bidirectional"))
      (node (ref "U2") (pin "P$4") (pinfunction "VCC_P$4") (pintype "bidirectional"))
      (node (ref "U5") (pin "12") (pinfunction "VCCIO_12") (pintype "power_in"))
      (node (ref "U5") (pin "24") (pinfunction "VCCIO_24") (pintype "power_in"))
      (node (ref "U5") (pin "39") (pinfunction "VCCD_39") (pintype "power_in"))
      (node (ref "U5") (pin "46") (pinfunction "VCCIO_46") (pintype "power_in"))
      (node (ref "U6") (pin "6") (pinfunction "VCC_6") (pintype "power_in"))
    )
    (net (code "14") (name "GND") (class "Default")
      (node (ref "C1") (pin "1") (pinfunction "P$1_1") (pintype "bidirectional"))
      (node (ref "C10") (pin "1") (pinfunction "P$1_1") (pintype "bidirectional"))
      (node (ref "C11") (pin "1") (pinfunction "P$1_1") (pintype "bidirectional"))
      (node (ref "C12") (pin "2") (pinfunction "2_2") (pintype "passive"))
      (node (ref "C13") (pin "2") (pinfunction "2_2") (pintype "passive"))
      (node (ref "C14") (pin "1") (pinfunction "P$1_1") (pintype "bidirectional"))
      (node (ref "C15") (pin "1") (pinfunction "P$1_1") (pintype "bidirectional"))
      (node (ref "C16") (pin "1") (pinfunction "P$1_1") (pintype "bidirectional"))
      (node (ref "C17") (pin "1") (pinfunction "P$1_1") (pintype "bidirectional"))
      (node (ref "C18") (pin "1") (pinfunction "P$1_1") (pintype "bidirectional"))
      (node (ref "C19") (pin "1") (pinfunction "P$1_1") (pintype "bidirectional"))
      (node (ref "C2") (pin "1") (pinfunction "P$1_1") (pintype "bidirectional"))
      (node (ref "C20") (pin "1") (pinfunction "P$1_1") (pintype "bidirectional"))
      (node (ref "C21") (pin "1") (pinfunction "P$1_1") (pintype "bidirectional"))
      (node (ref "C22") (pin "1") (pinfunction "P$1_1") (pintype "bidirectional"))
      (node (ref "C23") (pin "2") (pinfunction "2_2") (pintype "passive"))
      (node (ref "C24") (pin "2") (pinfunction "2_2") (pintype "passive"))
      (node (ref "C25") (pin "2") (pinfunction "2_2") (pintype "passive"))
      (node (ref "C26") (pin "2") (pinfunction "2_2") (pintype "passive"))
      (node (ref "C29") (pin "1") (pinfunction "P$1_1") (pintype "bidirectional"))
      (node (ref "C3") (pin "1") (pinfunction "P$1_1") (pintype "bidirectional"))
      (node (ref "C31") (pin "1") (pinfunction "P$1_1") (pintype "bidirectional"))
      (node (ref "C32") (pin "1") (pinfunction "P$1_1") (pintype "bidirectional"))
      (node (ref "C33") (pin "2") (pinfunction "2_2") (pintype "passive"))
      (node (ref "C34") (pin "1") (pinfunction "P$1_1") (pintype "bidirectional"))
      (node (ref "C35") (pin "1") (pinfunction "P$1_1") (pintype "bidirectional"))
      (node (ref "C36") (pin "1") (pinfunction "P$1_1") (pintype "bidirectional"))
      (node (ref "C37") (pin "1") (pinfunction "P$1_1") (pintype "bidirectional"))
      (node (ref "C38") (pin "1") (pinfunction "P$1_1") (pintype "bidirectional"))
      (node (ref "C39") (pin "1") (pinfunction "P$1_1") (pintype "bidirectional"))
      (node (ref "C4") (pin "1") (pinfunction "P$1_1") (pintype "bidirectional"))
      (node (ref "C40") (pin "2") (pinfunction "2_2") (pintype "passive"))
      (node (ref "C41") (pin "1") (pinfunction "P$1_1") (pintype "bidirectional"))
      (node (ref "C42") (pin "2") (pinfunction "2_2") (pintype "passive"))
      (node (ref "C43") (pin "1") (pinfunction "P$1_1") (pintype "bidirectional"))
      (node (ref "C44") (pin "2") (pinfunction "2_2") (pintype "passive"))
      (node (ref "C45") (pin "1") (pinfunction "P$1_1") (pintype "bidirectional"))
      (node (ref "C46") (pin "1") (pinfunction "P$1_1") (pintype "bidirectional"))
      (node (ref "C47") (pin "2") (pinfunction "2_2") (pintype "passive"))
      (node (ref "C49") (pin "1") (pinfunction "P$1_1") (pintype "bidirectional"))
      (node (ref "C5") (pin "1") (pinfunction "P$1_1") (pintype "bidirectional"))
      (node (ref "C50") (pin "1") (pinfunction "P$1_1") (pintype "bidirectional"))
      (node (ref "C51") (pin "1") (pinfunction "P$1_1") (pintype "bidirectional"))
      (node (ref "C52") (pin "1") (pinfunction "P$1_1") (pintype "bidirectional"))
      (node (ref "C53") (pin "1") (pinfunction "P$1_1") (pintype "bidirectional"))
      (node (ref "C54") (pin "1") (pinfunction "P$1_1") (pintype "bidirectional"))
      (node (ref "C55") (pin "1") (pinfunction "P$1_1") (pintype "bidirectional"))
      (node (ref "C56") (pin "1") (pinfunction "P$1_1") (pintype "bidirectional"))
      (node (ref "C57") (pin "1") (pinfunction "P$1_1") (pintype "bidirectional"))
      (node (ref "C58") (pin "1") (pinfunction "P$1_1") (pintype "bidirectional"))
      (node (ref "C59") (pin "1") (pinfunction "P$1_1") (pintype "bidirectional"))
      (node (ref "C6") (pin "1") (pinfunction "P$1_1") (pintype "bidirectional"))
      (node (ref "C60") (pin "1") (pinfunction "P$1_1") (pintype "bidirectional"))
      (node (ref "C61") (pin "1") (pinfunction "P$1_1") (pintype "bidirectional"))
      (node (ref "C62") (pin "1") (pinfunction "P$1_1") (pintype "bidirectional"))
      (node (ref "C7") (pin "1") (pinfunction "P$1_1") (pintype "bidirectional"))
      (node (ref "C8") (pin "1") (pinfunction "P$1_1") (pintype "bidirectional"))
      (node (ref "C9") (pin "1") (pinfunction "P$1_1") (pintype "bidirectional"))
      (node (ref "J1") (pin "P$15") (pinfunction "P$15_P$15") (pintype "bidirectional"))
      (node (ref "J1") (pin "P$2") (pinfunction "P$2_P$2") (pintype "bidirectional"))
      (node (ref "J2") (pin "5") (pinfunction "5_5") (pintype "passive"))
      (node (ref "J2") (pin "S1") (pinfunction "SHIELD_S1") (pintype "passive"))
      (node (ref "J2") (pin "S2") (pinfunction "SHIELD_S2") (pintype "passive"))
      (node (ref "J2") (pin "S3") (pinfunction "SHIELD_S3") (pintype "passive"))
      (node (ref "J2") (pin "S4") (pinfunction "SHIELD_S4") (pintype "passive"))
      (node (ref "J2") (pin "S5") (pinfunction "SHIELD_S5") (pintype "passive"))
      (node (ref "J2") (pin "S6") (pinfunction "SHIELD_S6") (pintype "passive"))
      (node (ref "J3") (pin "P$1") (pinfunction "P$1_P$1") (pintype "bidirectional"))
      (node (ref "JP10") (pin "2") (pinfunction "2_2") (pintype "passive"))
      (node (ref "JP11") (pin "2") (pinfunction "2_2") (pintype "passive"))
      (node (ref "JP12") (pin "2") (pinfunction "2_2") (pintype "passive"))
      (node (ref "JP15") (pin "2") (pinfunction "2_2") (pintype "passive"))
      (node (ref "JP21") (pin "2") (pinfunction "2_2") (pintype "passive"))
      (node (ref "JP31") (pin "2") (pinfunction "2_2") (pintype "passive"))
      (node (ref "JP40") (pin "10") (pinfunction "10_10") (pintype "passive"))
      (node (ref "JP40") (pin "12") (pinfunction "12_12") (pintype "passive"))
      (node (ref "JP40") (pin "14") (pinfunction "14_14") (pintype "passive"))
      (node (ref "JP40") (pin "16") (pinfunction "16_16") (pintype "passive"))
      (node (ref "JP40") (pin "18") (pinfunction "18_18") (pintype "passive"))
      (node (ref "JP40") (pin "2") (pinfunction "2_2") (pintype "passive"))
      (node (ref "JP40") (pin "20") (pinfunction "20_20") (pintype "passive"))
      (node (ref "JP40") (pin "22") (pinfunction "22_22") (pintype "passive"))
      (node (ref "JP40") (pin "24") (pinfunction "24_24") (pintype "passive"))
      (node (ref "JP40") (pin "26") (pinfunction "26_26") (pintype "passive"))
      (node (ref "JP40") (pin "28") (pinfunction "28_28") (pintype "passive"))
      (node (ref "JP40") (pin "30") (pinfunction "30_30") (pintype "passive"))
      (node (ref "JP40") (pin "4") (pinfunction "4_4") (pintype "passive"))
      (node (ref "JP40") (pin "6") (pinfunction "6_6") (pintype "passive"))
      (node (ref "JP40") (pin "8") (pinfunction "8_8") (pintype "passive"))
      (node (ref "JP41") (pin "10") (pinfunction "10_10") (pintype "passive"))
      (node (ref "JP41") (pin "12") (pinfunction "12_12") (pintype "passive"))
      (node (ref "JP41") (pin "14") (pinfunction "14_14") (pintype "passive"))
      (node (ref "JP41") (pin "16") (pinfunction "16_16") (pintype "passive"))
      (node (ref "JP41") (pin "2") (pinfunction "2_2") (pintype "passive"))
      (node (ref "JP41") (pin "4") (pinfunction "4_4") (pintype "passive"))
      (node (ref "JP41") (pin "6") (pinfunction "6_6") (pintype "passive"))
      (node (ref "JP41") (pin "8") (pinfunction "8_8") (pintype "passive"))
      (node (ref "LED5") (pin "C") (pinfunction "C_C") (pintype "passive"))
      (node (ref "R17") (pin "2") (pinfunction "P$2_2") (pintype "bidirectional"))
      (node (ref "R2") (pin "2") (pinfunction "P$2_2") (pintype "bidirectional"))
      (node (ref "R33") (pin "2") (pinfunction "P$2_2") (pintype "bidirectional"))
      (node (ref "R4") (pin "2") (pinfunction "P$2_2") (pintype "bidirectional"))
      (node (ref "R6") (pin "2") (pinfunction "P$2_2") (pintype "bidirectional"))
      (node (ref "R8") (pin "1") (pinfunction "P$1_1") (pintype "bidirectional"))
      (node (ref "SW1") (pin "P$3") (pinfunction "P$3_P$3") (pintype "bidirectional"))
      (node (ref "SW1") (pin "P$4") (pinfunction "P$4_P$4") (pintype "bidirectional"))
      (node (ref "SW2") (pin "P$3") (pinfunction "P$3_P$3") (pintype "bidirectional"))
      (node (ref "SW2") (pin "P$4") (pinfunction "P$4_P$4") (pintype "bidirectional"))
      (node (ref "TP0") (pin "TP") (pinfunction "TP_TP") (pintype "input"))
      (node (ref "TP17") (pin "TP") (pinfunction "TP_TP") (pintype "input"))
      (node (ref "TP18") (pin "TP") (pinfunction "TP_TP") (pintype "input"))
      (node (ref "U1") (pin "2") (pinfunction "GND_2") (pintype "bidirectional"))
      (node (ref "U10") (pin "2") (pinfunction "GND_2") (pintype "bidirectional"))
      (node (ref "U11") (pin "P$2") (pinfunction "GND_P$2") (pintype "bidirectional"))
      (node (ref "U12") (pin "P$2") (pinfunction "SEL_P$2") (pintype "bidirectional"))
      (node (ref "U12") (pin "P$3@0") (pinfunction "GND_P$3@0") (pintype "bidirectional"))
      (node (ref "U12") (pin "P$3@1") (pinfunction "GND_P$3@1") (pintype "bidirectional"))
      (node (ref "U12") (pin "P$3@2") (pinfunction "GND_P$3@2") (pintype "bidirectional"))
      (node (ref "U12") (pin "P$3@3") (pinfunction "GND_P$3@3") (pintype "bidirectional"))
      (node (ref "U13") (pin "P$3@0") (pinfunction "GND_P$3@0") (pintype "bidirectional"))
      (node (ref "U13") (pin "P$3@1") (pinfunction "GND_P$3@1") (pintype "bidirectional"))
      (node (ref "U13") (pin "P$3@2") (pinfunction "GND_P$3@2") (pintype "bidirectional"))
      (node (ref "U13") (pin "P$3@3") (pinfunction "GND_P$3@3") (pintype "bidirectional"))
      (node (ref "U14") (pin "P$4") (pinfunction "VSS_P$4") (pintype "bidirectional"))
      (node (ref "U15") (pin "P$4") (pinfunction "VSS_P$4") (pintype "bidirectional"))
      (node (ref "U16") (pin "4") (pinfunction "GND_4") (pintype "bidirectional"))
      (node (ref "U16") (pin "9") (pinfunction "PAD_9") (pintype "bidirectional"))
      (node (ref "U17") (pin "4") (pinfunction "GND_4") (pintype "bidirectional"))
      (node (ref "U17") (pin "9") (pinfunction "PAD_9") (pintype "bidirectional"))
      (node (ref "U2") (pin "P$2") (pinfunction "GND_P$2") (pintype "bidirectional"))
      (node (ref "U3") (pin "2") (pinfunction "GND_2") (pintype "bidirectional"))
      (node (ref "U4") (pin "2") (pinfunction "GND_2") (pintype "bidirectional"))
      (node (ref "U5") (pin "10") (pinfunction "GND_10") (pintype "power_in"))
      (node (ref "U5") (pin "11") (pinfunction "GND_11") (pintype "power_in"))
      (node (ref "U5") (pin "22") (pinfunction "GND_22") (pintype "power_in"))
      (node (ref "U5") (pin "23") (pinfunction "GND_23") (pintype "power_in"))
      (node (ref "U5") (pin "35") (pinfunction "GND_35") (pintype "power_in"))
      (node (ref "U5") (pin "36") (pinfunction "GND_36") (pintype "power_in"))
      (node (ref "U5") (pin "4") (pinfunction "AGND_4") (pintype "power_in"))
      (node (ref "U5") (pin "41") (pinfunction "AGND_41") (pintype "power_in"))
      (node (ref "U5") (pin "42") (pinfunction "TEST_42") (pintype "input"))
      (node (ref "U5") (pin "47") (pinfunction "GND_47") (pintype "power_in"))
      (node (ref "U5") (pin "48") (pinfunction "GND_48") (pintype "power_in"))
      (node (ref "U5") (pin "9") (pinfunction "AGND_9") (pintype "power_in"))
      (node (ref "U5") (pin "THERMAL") (pinfunction "PAD_THERMAL") (pintype "passive"))
      (node (ref "U6") (pin "2") (pinfunction "GND_2") (pintype "power_in"))
      (node (ref "U7") (pin "4") (pinfunction "VSS_4") (pintype "bidirectional"))
      (node (ref "U7") (pin "9") (pinfunction "PAD_9") (pintype "bidirectional"))
      (node (ref "U8") (pin "49") (pinfunction "49_49") (pintype "bidirectional"))
      (node (ref "U9") (pin "11") (pinfunction "GND_11") (pintype "bidirectional"))
    )
    (net (code "15") (name "HM01B0_+1V8") (class "Default")
      (node (ref "J1") (pin "P$10") (pinfunction "P$10_P$10") (pintype "bidirectional"))
      (node (ref "JP16") (pin "2") (pinfunction "2_2") (pintype "passive"))
      (node (ref "R28") (pin "1") (pinfunction "P$1_1") (pintype "bidirectional"))
      (node (ref "R29") (pin "1") (pinfunction "P$1_1") (pintype "bidirectional"))
    )
    (net (code "16") (name "HM01B0_+2V8") (class "Default")
      (node (ref "J1") (pin "P$11") (pinfunction "P$11_P$11") (pintype "bidirectional"))
      (node (ref "J1") (pin "P$4") (pinfunction "P$4_P$4") (pintype "bidirectional"))
      (node (ref "JP17") (pin "2") (pinfunction "2_2") (pintype "passive"))
    )
    (net (code "17") (name "HM01B0_D0") (class "Default")
      (node (ref "J1") (pin "P$14") (pinfunction "P$14_P$14") (pintype "bidirectional"))
      (node (ref "TP9") (pin "TP") (pinfunction "TP_TP") (pintype "input"))
      (node (ref "U8") (pin "35") (pinfunction "35_35") (pintype "bidirectional"))
    )
    (net (code "18") (name "HM01B0_D1") (class "Default")
      (node (ref "J1") (pin "P$3") (pinfunction "P$3_P$3") (pintype "bidirectional"))
      (node (ref "TP1") (pin "TP") (pinfunction "TP_TP") (pintype "input"))
      (node (ref "U8") (pin "23") (pinfunction "23_23") (pintype "bidirectional"))
    )
    (net (code "19") (name "HM01B0_D2") (class "Default")
      (node (ref "J1") (pin "P$9") (pinfunction "P$9_P$9") (pintype "bidirectional"))
      (node (ref "TP6") (pin "TP") (pinfunction "TP_TP") (pintype "input"))
      (node (ref "U8") (pin "31") (pinfunction "31_31") (pintype "bidirectional"))
    )
    (net (code "20") (name "HM01B0_D3") (class "Default")
      (node (ref "J1") (pin "P$5") (pinfunction "P$5_P$5") (pintype "bidirectional"))
      (node (ref "TP2") (pin "TP") (pinfunction "TP_TP") (pintype "input"))
      (node (ref "U8") (pin "25") (pinfunction "25_25") (pintype "bidirectional"))
    )
    (net (code "21") (name "HM01B0_D4") (class "Default")
      (node (ref "J1") (pin "P$12") (pinfunction "P$12_P$12") (pintype "bidirectional"))
      (node (ref "TP7") (pin "TP") (pinfunction "TP_TP") (pintype "input"))
      (node (ref "U8") (pin "32") (pinfunction "32_32") (pintype "bidirectional"))
    )
    (net (code "22") (name "HM01B0_D5") (class "Default")
      (node (ref "J1") (pin "P$20") (pinfunction "P$20_P$20") (pintype "bidirectional"))
      (node (ref "TP14") (pin "TP") (pinfunction "TP_TP") (pintype "input"))
      (node (ref "U8") (pin "40") (pinfunction "40_40") (pintype "bidirectional"))
    )
    (net (code "23") (name "HM01B0_D6") (class "Default")
      (node (ref "J1") (pin "P$19") (pinfunction "P$19_P$19") (pintype "bidirectional"))
      (node (ref "TP13") (pin "TP") (pinfunction "TP_TP") (pintype "input"))
      (node (ref "U8") (pin "39") (pinfunction "39_39") (pintype "bidirectional"))
    )
    (net (code "24") (name "HM01B0_D7") (class "Default")
      (node (ref "J1") (pin "P$13") (pinfunction "P$13_P$13") (pintype "bidirectional"))
      (node (ref "TP8") (pin "TP") (pinfunction "TP_TP") (pintype "input"))
      (node (ref "U8") (pin "34") (pinfunction "34_34") (pintype "bidirectional"))
    )
    (net (code "25") (name "HM01B0_HS") (class "Default")
      (node (ref "J1") (pin "P$16") (pinfunction "P$16_P$16") (pintype "bidirectional"))
      (node (ref "TP10") (pin "TP") (pinfunction "TP_TP") (pintype "input"))
      (node (ref "U8") (pin "36") (pinfunction "36_36") (pintype "bidirectional"))
    )
    (net (code "26") (name "HM01B0_INT") (class "Default")
      (node (ref "J1") (pin "P$18") (pinfunction "P$18_P$18") (pintype "bidirectional"))
      (node (ref "LED3") (pin "C") (pinfunction "C_C") (pintype "passive"))
      (node (ref "TP12") (pin "TP") (pinfunction "TP_TP") (pintype "input"))
      (node (ref "U8") (pin "38") (pinfunction "38_38") (pintype "bidirectional"))
    )
    (net (code "27") (name "HM01B0_MCK") (class "Default")
      (node (ref "J1") (pin "P$8") (pinfunction "P$8_P$8") (pintype "bidirectional"))
      (node (ref "TP5") (pin "TP") (pinfunction "TP_TP") (pintype "input"))
      (node (ref "U8") (pin "28") (pinfunction "28_28") (pintype "bidirectional"))
    )
    (net (code "28") (name "HM01B0_PCLK") (class "Default")
      (node (ref "J1") (pin "P$17") (pinfunction "P$17_P$17") (pintype "bidirectional"))
      (node (ref "TP11") (pin "TP") (pinfunction "TP_TP") (pintype "input"))
      (node (ref "U8") (pin "37") (pinfunction "37_37") (pintype "bidirectional"))
    )
    (net (code "29") (name "HM01B0_SCL") (class "Default")
      (node (ref "J1") (pin "P$21") (pinfunction "P$21_P$21") (pintype "bidirectional"))
      (node (ref "R29") (pin "2") (pinfunction "P$2_2") (pintype "bidirectional"))
      (node (ref "TP15") (pin "TP") (pinfunction "TP_TP") (pintype "input"))
      (node (ref "U8") (pin "41") (pinfunction "41_41") (pintype "bidirectional"))
    )
    (net (code "30") (name "HM01B0_SDA") (class "Default")
      (node (ref "J1") (pin "P$22") (pinfunction "P$22_P$22") (pintype "bidirectional"))
      (node (ref "R28") (pin "2") (pinfunction "P$2_2") (pintype "bidirectional"))
      (node (ref "TP16") (pin "TP") (pinfunction "TP_TP") (pintype "input"))
      (node (ref "U8") (pin "42") (pinfunction "42_42") (pintype "bidirectional"))
    )
    (net (code "31") (name "HM01B0_TRIG") (class "Default")
      (node (ref "J1") (pin "P$7") (pinfunction "P$7_P$7") (pintype "bidirectional"))
      (node (ref "LED4") (pin "C") (pinfunction "C_C") (pintype "passive"))
      (node (ref "TP4") (pin "TP") (pinfunction "TP_TP") (pintype "input"))
      (node (ref "U8") (pin "27") (pinfunction "27_27") (pintype "bidirectional"))
    )
    (net (code "32") (name "HM01B0_VS") (class "Default")
      (node (ref "J1") (pin "P$6") (pinfunction "P$6_P$6") (pintype "bidirectional"))
      (node (ref "TP3") (pin "TP") (pinfunction "TP_TP") (pintype "input"))
      (node (ref "U8") (pin "26") (pinfunction "26_26") (pintype "bidirectional"))
    )
    (net (code "33") (name "I2S_DATA") (class "Default")
      (node (ref "JP40") (pin "25") (pinfunction "25_25") (pintype "passive"))
      (node (ref "U12") (pin "P$6") (pinfunction "DATA_P$6") (pintype "bidirectional"))
      (node (ref "U13") (pin "P$6") (pinfunction "DATA_P$6") (pintype "bidirectional"))
      (node (ref "U8") (pin "18") (pinfunction "18_18") (pintype "bidirectional"))
    )
    (net (code "34") (name "ICE40_+1V2_CORE") (class "Default")
      (node (ref "C34") (pin "2") (pinfunction "P$2_2") (pintype "bidirectional"))
      (node (ref "C35") (pin "2") (pinfunction "P$2_2") (pintype "bidirectional"))
      (node (ref "C36") (pin "2") (pinfunction "P$2_2") (pintype "bidirectional"))
      (node (ref "C37") (pin "2") (pinfunction "P$2_2") (pintype "bidirectional"))
      (node (ref "JP5") (pin "2") (pinfunction "2_2") (pintype "passive"))
      (node (ref "U8") (pin "30") (pinfunction "30_30") (pintype "bidirectional"))
      (node (ref "U8") (pin "5") (pinfunction "5_5") (pintype "bidirectional"))
    )
    (net (code "35") (name "ICE40_+1V2_PLL") (class "Default")
      (node (ref "JP6") (pin "2") (pinfunction "2_2") (pintype "passive"))
      (node (ref "R25") (pin "1") (pinfunction "P$1_1") (pintype "bidirectional"))
    )
    (net (code "36") (name "ICE40_CRESETB") (class "Default")
      (node (ref "C54") (pin "2") (pinfunction "P$2_2") (pintype "bidirectional"))
      (node (ref "JP31") (pin "1") (pinfunction "1_1") (pintype "passive"))
      (node (ref "R26") (pin "2") (pinfunction "P$2_2") (pintype "bidirectional"))
      (node (ref "SW1") (pin "P$1") (pinfunction "P$1_P$1") (pintype "bidirectional"))
      (node (ref "SW1") (pin "P$2") (pinfunction "P$2_P$2") (pintype "bidirectional"))
      (node (ref "U5") (pin "20") (pinfunction "ADBUS7/RI#_20") (pintype "input"))
      (node (ref "U8") (pin "8") (pinfunction "8_8") (pintype "bidirectional"))
    )
    (net (code "37") (name "ICE40_FLASH_CIPO") (class "Default")
      (node (ref "JP40") (pin "9") (pinfunction "9_9") (pintype "passive"))
      (node (ref "U12") (pin "P$1") (pinfunction "WS_P$1") (pintype "bidirectional"))
      (node (ref "U13") (pin "P$1") (pinfunction "WS_P$1") (pintype "bidirectional"))
      (node (ref "U5") (pin "15") (pinfunction "ADBUS2/RTS#_15") (pintype "output"))
      (node (ref "U7") (pin "2") (pinfunction "DQ1_2") (pintype "bidirectional"))
      (node (ref "U8") (pin "17") (pinfunction "17_17") (pintype "bidirectional"))
    )
    (net (code "38") (name "ICE40_FLASH_COPI") (class "Default")
      (node (ref "JP40") (pin "5") (pinfunction "5_5") (pintype "passive"))
      (node (ref "U5") (pin "14") (pinfunction "ADBUS1/RXD_14") (pintype "input"))
      (node (ref "U7") (pin "5") (pinfunction "DQ0_5") (pintype "bidirectional"))
      (node (ref "U8") (pin "14") (pinfunction "14_14") (pintype "bidirectional"))
    )
    (net (code "39") (name "ICE40_FLASH_PS") (class "Default")
      (node (ref "JP40") (pin "1") (pinfunction "1_1") (pintype "passive"))
      (node (ref "R19") (pin "2") (pinfunction "P$2_2") (pintype "bidirectional"))
      (node (ref "U5") (pin "17") (pinfunction "ADBUS4/DTR#_17") (pintype "output"))
      (node (ref "U7") (pin "1") (pinfunction "S#_1") (pintype "bidirectional"))
      (node (ref "U8") (pin "16") (pinfunction "16_16") (pintype "bidirectional"))
    )
    (net (code "40") (name "ICE40_FLASH_SCK") (class "Default")
      (node (ref "JP40") (pin "3") (pinfunction "3_3") (pintype "passive"))
      (node (ref "R18") (pin "2") (pinfunction "P$2_2") (pintype "bidirectional"))
      (node (ref "U12") (pin "P$4") (pinfunction "BLK_P$4") (pintype "bidirectional"))
      (node (ref "U13") (pin "P$4") (pinfunction "BLK_P$4") (pintype "bidirectional"))
      (node (ref "U5") (pin "13") (pinfunction "ADBUS0/TXD_13") (pintype "output"))
      (node (ref "U7") (pin "6") (pinfunction "C_6") (pintype "bidirectional"))
      (node (ref "U8") (pin "15") (pinfunction "15_15") (pintype "bidirectional"))
    )
    (net (code "41") (name "ICE40_GPIO43") (class "Default")
      (node (ref "LED5") (pin "A") (pinfunction "A_A") (pintype "passive"))
      (node (ref "R38") (pin "2") (pinfunction "P$2_2") (pintype "bidirectional"))
      (node (ref "SW2") (pin "P$1") (pinfunction "P$1_P$1") (pintype "bidirectional"))
      (node (ref "SW2") (pin "P$2") (pinfunction "P$2_P$2") (pintype "bidirectional"))
      (node (ref "U8") (pin "43") (pinfunction "43_43") (pintype "bidirectional"))
    )
    (net (code "42") (name "ICE40_OSC_12M") (class "Default")
      (node (ref "JP40") (pin "23") (pinfunction "23_23") (pintype "passive"))
      (node (ref "U11") (pin "P$3") (pinfunction "OUT_P$3") (pintype "bidirectional"))
      (node (ref "U8") (pin "20") (pinfunction "20_20") (pintype "bidirectional"))
    )
    (net (code "43") (name "ICE40_OSC_VCC") (class "Default")
      (node (ref "C49") (pin "2") (pinfunction "P$2_2") (pintype "bidirectional"))
      (node (ref "JP19") (pin "2") (pinfunction "2_2") (pintype "passive"))
      (node (ref "R31") (pin "1") (pinfunction "P$1_1") (pintype "bidirectional"))
      (node (ref "U11") (pin "P$4") (pinfunction "VCC_P$4") (pintype "bidirectional"))
    )
    (net (code "44") (name "ICE40_SPI_VCCIO1") (class "Default")
      (node (ref "C39") (pin "2") (pinfunction "P$2_2") (pintype "bidirectional"))
      (node (ref "C40") (pin "1") (pinfunction "1_1") (pintype "passive"))
      (node (ref "JP8") (pin "2") (pinfunction "2_2") (pintype "passive"))
      (node (ref "R26") (pin "1") (pinfunction "P$1_1") (pintype "bidirectional"))
      (node (ref "U8") (pin "22") (pinfunction "22_22") (pintype "bidirectional"))
    )
    (net (code "45") (name "ICE40_VCCIO0") (class "Default")
      (node (ref "C41") (pin "2") (pinfunction "P$2_2") (pintype "bidirectional"))
      (node (ref "C42") (pin "1") (pinfunction "1_1") (pintype "passive"))
      (node (ref "JP13") (pin "2") (pinfunction "2_2") (pintype "passive"))
      (node (ref "JP9") (pin "2") (pinfunction "2_2") (pintype "passive"))
      (node (ref "U8") (pin "33") (pinfunction "33_33") (pintype "bidirectional"))
    )
    (net (code "46") (name "ICE40_VCCIO2") (class "Default")
      (node (ref "C43") (pin "2") (pinfunction "P$2_2") (pintype "bidirectional"))
      (node (ref "C44") (pin "1") (pinfunction "1_1") (pintype "passive"))
      (node (ref "JP14") (pin "2") (pinfunction "2_2") (pintype "passive"))
      (node (ref "JP20") (pin "2") (pinfunction "2_2") (pintype "passive"))
      (node (ref "U8") (pin "1") (pinfunction "1_1") (pintype "bidirectional"))
    )
    (net (code "47") (name "ICE40_VPP2V5_+3V3") (class "Default")
      (node (ref "C38") (pin "2") (pinfunction "P$2_2") (pintype "bidirectional"))
      (node (ref "JP7") (pin "2") (pinfunction "2_2") (pintype "passive"))
      (node (ref "U8") (pin "24") (pinfunction "24_24") (pintype "bidirectional"))
    )
    (net (code "48") (name "MEM1_CIPO") (class "Default")
      (node (ref "JP40") (pin "7") (pinfunction "7_7") (pintype "passive"))
      (node (ref "U16") (pin "2") (pinfunction "SO/DQ1_2") (pintype "bidirectional"))
      (node (ref "U17") (pin "2") (pinfunction "SO/DQ1_2") (pintype "bidirectional"))
      (node (ref "U8") (pin "6") (pinfunction "6_6") (pintype "bidirectional"))
    )
    (net (code "49") (name "MEM1_COPI") (class "Default")
      (node (ref "JP40") (pin "21") (pinfunction "21_21") (pintype "passive"))
      (node (ref "U16") (pin "5") (pinfunction "SI/DQ0_5") (pintype "bidirectional"))
      (node (ref "U17") (pin "5") (pinfunction "SI/DQ0_5") (pintype "bidirectional"))
      (node (ref "U8") (pin "12") (pinfunction "12_12") (pintype "bidirectional"))
    )
    (net (code "50") (name "MEM1_PS1") (class "Default")
      (node (ref "JP40") (pin "11") (pinfunction "11_11") (pintype "passive"))
      (node (ref "U16") (pin "1") (pinfunction "~{CS}_1") (pintype "bidirectional"))
      (node (ref "U8") (pin "9") (pinfunction "9_9") (pintype "bidirectional"))
    )
    (net (code "51") (name "MEM1_PS2") (class "Default")
      (node (ref "JP40") (pin "13") (pinfunction "13_13") (pintype "passive"))
      (node (ref "U17") (pin "1") (pinfunction "~{CS}_1") (pintype "bidirectional"))
      (node (ref "U8") (pin "13") (pinfunction "13_13") (pintype "bidirectional"))
    )
    (net (code "52") (name "MEM1_SCK") (class "Default")
      (node (ref "JP40") (pin "19") (pinfunction "19_19") (pintype "passive"))
      (node (ref "U16") (pin "6") (pinfunction "SCK_6") (pintype "bidirectional"))
      (node (ref "U17") (pin "6") (pinfunction "SCK_6") (pintype "bidirectional"))
      (node (ref "U8") (pin "11") (pinfunction "11_11") (pintype "bidirectional"))
    )
    (net (code "53") (name "MEM1_VCC1") (class "Default")
      (node (ref "C59") (pin "2") (pinfunction "P$2_2") (pintype "bidirectional"))
      (node (ref "C60") (pin "2") (pinfunction "P$2_2") (pintype "bidirectional"))
      (node (ref "JP23") (pin "2") (pinfunction "2_2") (pintype "passive"))
      (node (ref "U16") (pin "8") (pinfunction "VCC_8") (pintype "bidirectional"))
    )
    (net (code "54") (name "MEM1_VCC2") (class "Default")
      (node (ref "C61") (pin "2") (pinfunction "P$2_2") (pintype "bidirectional"))
      (node (ref "C62") (pin "2") (pinfunction "P$2_2") (pintype "bidirectional"))
      (node (ref "JP24") (pin "2") (pinfunction "2_2") (pintype "passive"))
      (node (ref "U17") (pin "8") (pinfunction "VCC_8") (pintype "bidirectional"))
    )
    (net (code "55") (name "MEM1_~{HOLD}") (class "Default")
      (node (ref "JP40") (pin "17") (pinfunction "17_17") (pintype "passive"))
      (node (ref "U16") (pin "7") (pinfunction "~{HOLD}/DQ3_7") (pintype "bidirectional"))
      (node (ref "U17") (pin "7") (pinfunction "~{HOLD}/DQ3_7") (pintype "bidirectional"))
      (node (ref "U8") (pin "10") (pinfunction "10_10") (pintype "bidirectional"))
    )
    (net (code "56") (name "MEM1_~{WP}") (class "Default")
      (node (ref "JP40") (pin "15") (pinfunction "15_15") (pintype "passive"))
      (node (ref "U16") (pin "3") (pinfunction "~{WP}/DQ2_3") (pintype "bidirectional"))
      (node (ref "U17") (pin "3") (pinfunction "~{WP}/DQ2_3") (pintype "bidirectional"))
      (node (ref "U8") (pin "7") (pinfunction "7_7") (pintype "bidirectional"))
    )
    (net (code "57") (name "MEM2_CIPO1") (class "Default")
      (node (ref "JP41") (pin "3") (pinfunction "3_3") (pintype "passive"))
      (node (ref "U14") (pin "P$2") (pinfunction "SO_P$2") (pintype "bidirectional"))
      (node (ref "U8") (pin "45") (pinfunction "45_45") (pintype "bidirectional"))
    )
    (net (code "58") (name "MEM2_CIPO2") (class "Default")
      (node (ref "JP41") (pin "11") (pinfunction "11_11") (pintype "passive"))
      (node (ref "U15") (pin "P$2") (pinfunction "SO_P$2") (pintype "bidirectional"))
      (node (ref "U8") (pin "48") (pinfunction "48_48") (pintype "bidirectional"))
    )
    (net (code "59") (name "MEM2_COPI1") (class "Default")
      (node (ref "JP41") (pin "7") (pinfunction "7_7") (pintype "passive"))
      (node (ref "U14") (pin "P$5") (pinfunction "SI_P$5") (pintype "bidirectional"))
      (node (ref "U8") (pin "46") (pinfunction "46_46") (pintype "bidirectional"))
    )
    (net (code "60") (name "MEM2_COPI2") (class "Default")
      (node (ref "JP41") (pin "15") (pinfunction "15_15") (pintype "passive"))
      (node (ref "U15") (pin "P$5") (pinfunction "SI_P$5") (pintype "bidirectional"))
      (node (ref "U8") (pin "4") (pinfunction "4_4") (pintype "bidirectional"))
    )
    (net (code "61") (name "MEM2_PS1") (class "Default")
      (node (ref "JP41") (pin "1") (pinfunction "1_1") (pintype "passive"))
      (node (ref "U14") (pin "P$1") (pinfunction "~{CS}_P$1") (pintype "bidirectional"))
      (node (ref "U8") (pin "44") (pinfunction "44_44") (pintype "bidirectional"))
    )
    (net (code "62") (name "MEM2_PS2") (class "Default")
      (node (ref "JP41") (pin "9") (pinfunction "9_9") (pintype "passive"))
      (node (ref "U15") (pin "P$1") (pinfunction "~{CS}_P$1") (pintype "bidirectional"))
      (node (ref "U8") (pin "47") (pinfunction "47_47") (pintype "bidirectional"))
    )
    (net (code "63") (name "MEM2_SCK") (class "Default")
      (node (ref "JP41") (pin "13") (pinfunction "13_13") (pintype "passive"))
      (node (ref "U14") (pin "P$6") (pinfunction "SCK_P$6") (pintype "bidirectional"))
      (node (ref "U15") (pin "P$6") (pinfunction "SCK_P$6") (pintype "bidirectional"))
      (node (ref "U8") (pin "3") (pinfunction "3_3") (pintype "bidirectional"))
    )
    (net (code "64") (name "MEM2_VCC1") (class "Default")
      (node (ref "C55") (pin "2") (pinfunction "P$2_2") (pintype "bidirectional"))
      (node (ref "C57") (pin "2") (pinfunction "P$2_2") (pintype "bidirectional"))
      (node (ref "JP25") (pin "2") (pinfunction "2_2") (pintype "passive"))
      (node (ref "JP26") (pin "2") (pinfunction "2_2") (pintype "passive"))
      (node (ref "U14") (pin "P$7") (pinfunction "~{HOLD}_P$7") (pintype "bidirectional"))
      (node (ref "U14") (pin "P$8") (pinfunction "VDD_P$8") (pintype "bidirectional"))
    )
    (net (code "65") (name "MEM2_VCC2") (class "Default")
      (node (ref "C56") (pin "2") (pinfunction "P$2_2") (pintype "bidirectional"))
      (node (ref "C58") (pin "2") (pinfunction "P$2_2") (pintype "bidirectional"))
      (node (ref "JP27") (pin "2") (pinfunction "2_2") (pintype "passive"))
      (node (ref "JP28") (pin "2") (pinfunction "2_2") (pintype "passive"))
      (node (ref "U15") (pin "P$7") (pinfunction "~{HOLD}_P$7") (pintype "bidirectional"))
      (node (ref "U15") (pin "P$8") (pinfunction "VDD_P$8") (pintype "bidirectional"))
    )
    (net (code "66") (name "MEM2_~{WP}") (class "Default")
      (node (ref "JP41") (pin "5") (pinfunction "5_5") (pintype "passive"))
      (node (ref "U14") (pin "P$3") (pinfunction "~{WP}_P$3") (pintype "bidirectional"))
      (node (ref "U15") (pin "P$3") (pinfunction "~{WP}_P$3") (pintype "bidirectional"))
      (node (ref "U8") (pin "2") (pinfunction "2_2") (pintype "bidirectional"))
    )
    (net (code "67") (name "MIC1_VCC") (class "Default")
      (node (ref "C50") (pin "2") (pinfunction "P$2_2") (pintype "bidirectional"))
      (node (ref "C51") (pin "2") (pinfunction "P$2_2") (pintype "bidirectional"))
      (node (ref "JP29") (pin "2") (pinfunction "2_2") (pintype "passive"))
      (node (ref "U12") (pin "P$5") (pinfunction "VDD_P$5") (pintype "bidirectional"))
    )
    (net (code "68") (name "MIC2_VCC") (class "Default")
      (node (ref "C52") (pin "2") (pinfunction "P$2_2") (pintype "bidirectional"))
      (node (ref "C53") (pin "2") (pinfunction "P$2_2") (pintype "bidirectional"))
      (node (ref "JP30") (pin "2") (pinfunction "2_2") (pintype "passive"))
      (node (ref "U13") (pin "P$5") (pinfunction "VDD_P$5") (pintype "bidirectional"))
    )
    (net (code "69") (name "Net-(C4-P$2)") (class "Default")
      (node (ref "C4") (pin "2") (pinfunction "P$2_2") (pintype "bidirectional"))
      (node (ref "U5") (pin "37") (pinfunction "VCCA_37") (pintype "power_in"))
    )
    (net (code "70") (name "Net-(C5-P$2)") (class "Default")
      (node (ref "C5") (pin "2") (pinfunction "P$2_2") (pintype "bidirectional"))
      (node (ref "U5") (pin "38") (pinfunction "VCCCORE_38") (pintype "power_in"))
    )
    (net (code "71") (name "Net-(C17-P$2)") (class "Default")
      (node (ref "C17") (pin "2") (pinfunction "P$2_2") (pintype "bidirectional"))
      (node (ref "FB1") (pin "2") (pinfunction "P$2_2") (pintype "bidirectional"))
      (node (ref "U5") (pin "8") (pinfunction "VPLL_8") (pintype "power_in"))
    )
    (net (code "72") (name "Net-(C18-P$2)") (class "Default")
      (node (ref "C18") (pin "2") (pinfunction "P$2_2") (pintype "bidirectional"))
      (node (ref "FB2") (pin "2") (pinfunction "P$2_2") (pintype "bidirectional"))
      (node (ref "U5") (pin "3") (pinfunction "VPHY_3") (pintype "power_in"))
    )
    (net (code "73") (name "Net-(C21-P$2)") (class "Default")
      (node (ref "C21") (pin "2") (pinfunction "P$2_2") (pintype "bidirectional"))
      (node (ref "R10") (pin "2") (pinfunction "P$2_2") (pintype "bidirectional"))
      (node (ref "U5") (pin "34") (pinfunction "~{RESET}_34") (pintype "input"))
    )
    (net (code "74") (name "Net-(C32-P$2)") (class "Default")
      (node (ref "C32") (pin "2") (pinfunction "P$2_2") (pintype "bidirectional"))
      (node (ref "C33") (pin "1") (pinfunction "1_1") (pintype "passive"))
      (node (ref "R25") (pin "2") (pinfunction "P$2_2") (pintype "bidirectional"))
      (node (ref "U8") (pin "29") (pinfunction "29_29") (pintype "bidirectional"))
    )
    (net (code "75") (name "Net-(R1-P$2)") (class "Default")
      (node (ref "R1") (pin "2") (pinfunction "P$2_2") (pintype "bidirectional"))
      (node (ref "R2") (pin "1") (pinfunction "P$1_1") (pintype "bidirectional"))
      (node (ref "U1") (pin "4") (pinfunction "ADJ_4") (pintype "bidirectional"))
    )
    (net (code "76") (name "Net-(R3-P$2)") (class "Default")
      (node (ref "R3") (pin "2") (pinfunction "P$2_2") (pintype "bidirectional"))
      (node (ref "R4") (pin "1") (pinfunction "P$1_1") (pintype "bidirectional"))
      (node (ref "U3") (pin "4") (pinfunction "ADJ_4") (pintype "bidirectional"))
    )
    (net (code "77") (name "Net-(R5-P$2)") (class "Default")
      (node (ref "R5") (pin "2") (pinfunction "P$2_2") (pintype "bidirectional"))
      (node (ref "R6") (pin "1") (pinfunction "P$1_1") (pintype "bidirectional"))
      (node (ref "U4") (pin "4") (pinfunction "ADJ_4") (pintype "bidirectional"))
    )
    (net (code "78") (name "Net-(R7-P$2)") (class "Default")
      (node (ref "R7") (pin "2") (pinfunction "P$2_2") (pintype "bidirectional"))
      (node (ref "U2") (pin "P$1") (pinfunction "STBY_P$1") (pintype "bidirectional"))
    )
    (net (code "79") (name "Net-(R8-P$2)") (class "Default")
      (node (ref "R8") (pin "2") (pinfunction "P$2_2") (pintype "bidirectional"))
      (node (ref "U5") (pin "5") (pinfunction "REF_5") (pintype "input"))
    )
    (net (code "80") (name "Net-(R9-P$2)") (class "Default")
      (node (ref "R9") (pin "2") (pinfunction "P$2_2") (pintype "bidirectional"))
      (node (ref "U5") (pin "43") (pinfunction "EEDATA_43") (pintype "bidirectional"))
      (node (ref "U6") (pin "3") (pinfunction "DI_3") (pintype "input"))
    )
    (net (code "81") (name "Net-(R11-P$2)") (class "Default")
      (node (ref "R11") (pin "2") (pinfunction "P$2_2") (pintype "bidirectional"))
      (node (ref "R9") (pin "1") (pinfunction "P$1_1") (pintype "bidirectional"))
      (node (ref "U6") (pin "1") (pinfunction "DO_1") (pintype "tri_state"))
    )
    (net (code "82") (name "Net-(R12-P$2)") (class "Default")
      (node (ref "R12") (pin "2") (pinfunction "P$2_2") (pintype "bidirectional"))
      (node (ref "U5") (pin "44") (pinfunction "EECLK_44") (pintype "output"))
      (node (ref "U6") (pin "4") (pinfunction "CLK_4") (pintype "input"))
    )
    (net (code "83") (name "Net-(R13-P$2)") (class "Default")
      (node (ref "R13") (pin "2") (pinfunction "P$2_2") (pintype "bidirectional"))
      (node (ref "U5") (pin "45") (pinfunction "EECS_45") (pintype "bidirectional"))
      (node (ref "U6") (pin "5") (pinfunction "CS_5") (pintype "input"))
    )
    (net (code "84") (name "Net-(R14-P$1)") (class "Default")
      (node (ref "R14") (pin "1") (pinfunction "P$1_1") (pintype "bidirectional"))
      (node (ref "U5") (pin "32") (pinfunction "ACBUS8_32") (pintype "bidirectional"))
    )
    (net (code "85") (name "Net-(R14-P$2)") (class "Default")
      (node (ref "LED1") (pin "C") (pinfunction "C_C") (pintype "passive"))
      (node (ref "R14") (pin "2") (pinfunction "P$2_2") (pintype "bidirectional"))
    )
    (net (code "86") (name "Net-(R15-P$1)") (class "Default")
      (node (ref "R15") (pin "1") (pinfunction "P$1_1") (pintype "bidirectional"))
      (node (ref "U5") (pin "33") (pinfunction "ACBUS9_33") (pintype "bidirectional"))
    )
    (net (code "87") (name "Net-(R15-P$2)") (class "Default")
      (node (ref "LED2") (pin "C") (pinfunction "C_C") (pintype "passive"))
      (node (ref "R15") (pin "2") (pinfunction "P$2_2") (pintype "bidirectional"))
    )
    (net (code "88") (name "Net-(R16-P$2)") (class "Default")
      (node (ref "R16") (pin "2") (pinfunction "P$2_2") (pintype "bidirectional"))
      (node (ref "R17") (pin "1") (pinfunction "P$1_1") (pintype "bidirectional"))
      (node (ref "U5") (pin "31") (pinfunction "ACBUS7_31") (pintype "bidirectional"))
    )
    (net (code "89") (name "Net-(R20-P$2)") (class "Default")
      (node (ref "R20") (pin "2") (pinfunction "P$2_2") (pintype "bidirectional"))
      (node (ref "U7") (pin "3") (pinfunction "W#/DQ2_3") (pintype "bidirectional"))
    )
    (net (code "90") (name "Net-(R21-P$2)") (class "Default")
      (node (ref "R21") (pin "2") (pinfunction "P$2_2") (pintype "bidirectional"))
      (node (ref "U7") (pin "7") (pinfunction "DQ3/HOLD#_7") (pintype "bidirectional"))
    )
    (net (code "91") (name "Net-(R27-P$2)") (class "Default")
      (node (ref "LED3") (pin "A") (pinfunction "A_A") (pintype "passive"))
      (node (ref "R27") (pin "2") (pinfunction "P$2_2") (pintype "bidirectional"))
    )
    (net (code "92") (name "Net-(R30-P$2)") (class "Default")
      (node (ref "R30") (pin "2") (pinfunction "P$2_2") (pintype "bidirectional"))
      (node (ref "R33") (pin "1") (pinfunction "P$1_1") (pintype "bidirectional"))
      (node (ref "U10") (pin "4") (pinfunction "ADJ_4") (pintype "bidirectional"))
    )
    (net (code "93") (name "Net-(R31-P$2)") (class "Default")
      (node (ref "JP21") (pin "1") (pinfunction "1_1") (pintype "passive"))
      (node (ref "R31") (pin "2") (pinfunction "P$2_2") (pintype "bidirectional"))
      (node (ref "U11") (pin "P$1") (pinfunction "STBY_P$1") (pintype "bidirectional"))
    )
    (net (code "94") (name "Net-(R37-P$2)") (class "Default")
      (node (ref "LED4") (pin "A") (pinfunction "A_A") (pintype "passive"))
      (node (ref "R37") (pin "2") (pinfunction "P$2_2") (pintype "bidirectional"))
    )
    (net (code "95") (name "Net-(U9-IN+1)") (class "Default")
      (node (ref "JP3") (pin "2") (pinfunction "2_2") (pintype "passive"))
      (node (ref "R24") (pin "1") (pinfunction "1_1") (pintype "passive"))
      (node (ref "U9") (pin "3") (pinfunction "IN+1_3") (pintype "bidirectional"))
    )
    (net (code "96") (name "Net-(U9-IN+2)") (class "Default")
      (node (ref "JP2") (pin "2") (pinfunction "2_2") (pintype "passive"))
      (node (ref "R23") (pin "1") (pinfunction "1_1") (pintype "passive"))
      (node (ref "U9") (pin "5") (pinfunction "IN+2_5") (pintype "bidirectional"))
    )
    (net (code "97") (name "Net-(U9-IN+3)") (class "Default")
      (node (ref "JP1") (pin "2") (pinfunction "2_2") (pintype "passive"))
      (node (ref "R22") (pin "1") (pinfunction "1_1") (pintype "passive"))
      (node (ref "U9") (pin "10") (pinfunction "IN+3_10") (pintype "bidirectional"))
    )
    (net (code "98") (name "Net-(U9-IN+4)") (class "Default")
      (node (ref "JP18") (pin "2") (pinfunction "2_2") (pintype "passive"))
      (node (ref "R32") (pin "1") (pinfunction "1_1") (pintype "passive"))
      (node (ref "U9") (pin "12") (pinfunction "IN+4_12") (pintype "bidirectional"))
    )
    (net (code "99") (name "Net-(U9-OUT1)") (class "Default")
      (node (ref "JP10") (pin "1") (pinfunction "1_1") (pintype "passive"))
      (node (ref "U9") (pin "1") (pinfunction "OUT1_1") (pintype "bidirectional"))
    )
    (net (code "100") (name "Net-(U9-OUT2)") (class "Default")
      (node (ref "JP11") (pin "1") (pinfunction "1_1") (pintype "passive"))
      (node (ref "U9") (pin "7") (pinfunction "OUT2_7") (pintype "bidirectional"))
    )
    (net (code "101") (name "Net-(U9-OUT3)") (class "Default")
      (node (ref "JP12") (pin "1") (pinfunction "1_1") (pintype "passive"))
      (node (ref "U9") (pin "8") (pinfunction "OUT3_8") (pintype "bidirectional"))
    )
    (net (code "102") (name "Net-(U9-OUT4)") (class "Default")
      (node (ref "JP15") (pin "1") (pinfunction "1_1") (pintype "passive"))
      (node (ref "U9") (pin "14") (pinfunction "OUT4_14") (pintype "bidirectional"))
    )
    (net (code "103") (name "QWIIC_+3V3") (class "Default")
      (node (ref "J3") (pin "P$2") (pinfunction "P$2_P$2") (pintype "bidirectional"))
      (node (ref "JP22") (pin "2") (pinfunction "2_2") (pintype "passive"))
      (node (ref "R34") (pin "1") (pinfunction "P$1_1") (pintype "bidirectional"))
      (node (ref "R35") (pin "1") (pinfunction "P$1_1") (pintype "bidirectional"))
    )
    (net (code "104") (name "QWIIC_SCL") (class "Default")
      (node (ref "J3") (pin "P$4") (pinfunction "P$4_P$4") (pintype "bidirectional"))
      (node (ref "JP40") (pin "27") (pinfunction "27_27") (pintype "passive"))
      (node (ref "R35") (pin "2") (pinfunction "P$2_2") (pintype "bidirectional"))
      (node (ref "U8") (pin "21") (pinfunction "21_21") (pintype "bidirectional"))
    )
    (net (code "105") (name "QWIIC_SDA") (class "Default")
      (node (ref "J3") (pin "P$3") (pinfunction "P$3_P$3") (pintype "bidirectional"))
      (node (ref "JP40") (pin "29") (pinfunction "29_29") (pintype "passive"))
      (node (ref "R34") (pin "2") (pinfunction "P$2_2") (pintype "bidirectional"))
      (node (ref "U8") (pin "19") (pinfunction "19_19") (pintype "bidirectional"))
    )
    (net (code "106") (name "VUSB") (class "Default")
      (node (ref "C1") (pin "2") (pinfunction "P$2_2") (pintype "bidirectional"))
      (node (ref "C10") (pin "2") (pinfunction "P$2_2") (pintype "bidirectional"))
      (node (ref "C12") (pin "1") (pinfunction "1_1") (pintype "passive"))
      (node (ref "C2") (pin "2") (pinfunction "P$2_2") (pintype "bidirectional"))
      (node (ref "C45") (pin "2") (pinfunction "P$2_2") (pintype "bidirectional"))
      (node (ref "C6") (pin "2") (pinfunction "P$2_2") (pintype "bidirectional"))
      (node (ref "C8") (pin "2") (pinfunction "P$2_2") (pintype "bidirectional"))
      (node (ref "J2") (pin "1") (pinfunction "1_1") (pintype "passive"))
      (node (ref "R16") (pin "1") (pinfunction "P$1_1") (pintype "bidirectional"))
      (node (ref "U1") (pin "1") (pinfunction "VIN_1") (pintype "bidirectional"))
      (node (ref "U1") (pin "3") (pinfunction "EN_3") (pintype "bidirectional"))
      (node (ref "U10") (pin "1") (pinfunction "VIN_1") (pintype "bidirectional"))
      (node (ref "U10") (pin "3") (pinfunction "EN_3") (pintype "bidirectional"))
      (node (ref "U3") (pin "1") (pinfunction "VIN_1") (pintype "bidirectional"))
      (node (ref "U3") (pin "3") (pinfunction "EN_3") (pintype "bidirectional"))
      (node (ref "U4") (pin "1") (pinfunction "VIN_1") (pintype "bidirectional"))
      (node (ref "U4") (pin "3") (pinfunction "EN_3") (pintype "bidirectional"))
      (node (ref "U5") (pin "40") (pinfunction "VREGIN_40") (pintype "power_in"))
    )
    (net (code "107") (name "unconnected-(J1-PadP$1)") (class "Default")
      (node (ref "J1") (pin "P$1") (pinfunction "P$1_P$1") (pintype "bidirectional"))
    )
    (net (code "108") (name "unconnected-(J1-PadP$23)") (class "Default")
      (node (ref "J1") (pin "P$23") (pinfunction "P$23_P$23") (pintype "bidirectional"))
    )
    (net (code "109") (name "unconnected-(J1-PadP$24)") (class "Default")
      (node (ref "J1") (pin "P$24") (pinfunction "P$24_P$24") (pintype "bidirectional"))
    )
    (net (code "110") (name "unconnected-(J2-Pad4)") (class "Default")
      (node (ref "J2") (pin "4") (pinfunction "4_4") (pintype "passive"))
    )
    (net (code "111") (name "unconnected-(U5-ACBUS0{slash}TXDEN-Pad21)") (class "Default")
      (node (ref "U5") (pin "21") (pinfunction "ACBUS0/TXDEN_21") (pintype "bidirectional"))
    )
    (net (code "112") (name "unconnected-(U5-ACBUS1-Pad25)") (class "Default")
      (node (ref "U5") (pin "25") (pinfunction "ACBUS1_25") (pintype "bidirectional"))
    )
    (net (code "113") (name "unconnected-(U5-ACBUS2-Pad26)") (class "Default")
      (node (ref "U5") (pin "26") (pinfunction "ACBUS2_26") (pintype "bidirectional"))
    )
    (net (code "114") (name "unconnected-(U5-ACBUS3{slash}RXLED#-Pad27)") (class "Default")
      (node (ref "U5") (pin "27") (pinfunction "ACBUS3/RXLED#_27") (pintype "bidirectional"))
    )
    (net (code "115") (name "unconnected-(U5-ACBUS4{slash}TXLED#-Pad28)") (class "Default")
      (node (ref "U5") (pin "28") (pinfunction "ACBUS4/TXLED#_28") (pintype "bidirectional"))
    )
    (net (code "116") (name "unconnected-(U5-ACBUS5-Pad29)") (class "Default")
      (node (ref "U5") (pin "29") (pinfunction "ACBUS5_29") (pintype "bidirectional"))
    )
    (net (code "117") (name "unconnected-(U5-ACBUS6-Pad30)") (class "Default")
      (node (ref "U5") (pin "30") (pinfunction "ACBUS6_30") (pintype "bidirectional"))
    )
    (net (code "118") (name "unconnected-(U5-ADBUS3{slash}CTS#-Pad16)") (class "Default")
      (node (ref "U5") (pin "16") (pinfunction "ADBUS3/CTS#_16") (pintype "input"))
    )
    (net (code "119") (name "unconnected-(U5-ADBUS5{slash}DSR#-Pad18)") (class "Default")
      (node (ref "U5") (pin "18") (pinfunction "ADBUS5/DSR#_18") (pintype "input"))
    )
    (net (code "120") (name "unconnected-(U5-ADBUS6{slash}DCD#-Pad19)") (class "Default")
      (node (ref "U5") (pin "19") (pinfunction "ADBUS6/DCD#_19") (pintype "input"))
    )
    (net (code "121") (name "unconnected-(U5-OSCOUT-Pad2)") (class "Default")
      (node (ref "U5") (pin "2") (pinfunction "OSCOUT_2") (pintype "output"))
    )
    (net (code "122") (name "unconnected-(U14-NCPAD-PadP$9)") (class "Default")
      (node (ref "U14") (pin "P$9") (pinfunction "NCPAD_P$9") (pintype "bidirectional"))
    )
    (net (code "123") (name "unconnected-(U15-NCPAD-PadP$9)") (class "Default")
      (node (ref "U15") (pin "P$9") (pinfunction "NCPAD_P$9") (pintype "bidirectional"))
    )
  )
)
